# Sheet_1_2024-10-24.net
KiCad netlist of a schematic drawn in Altium Designer
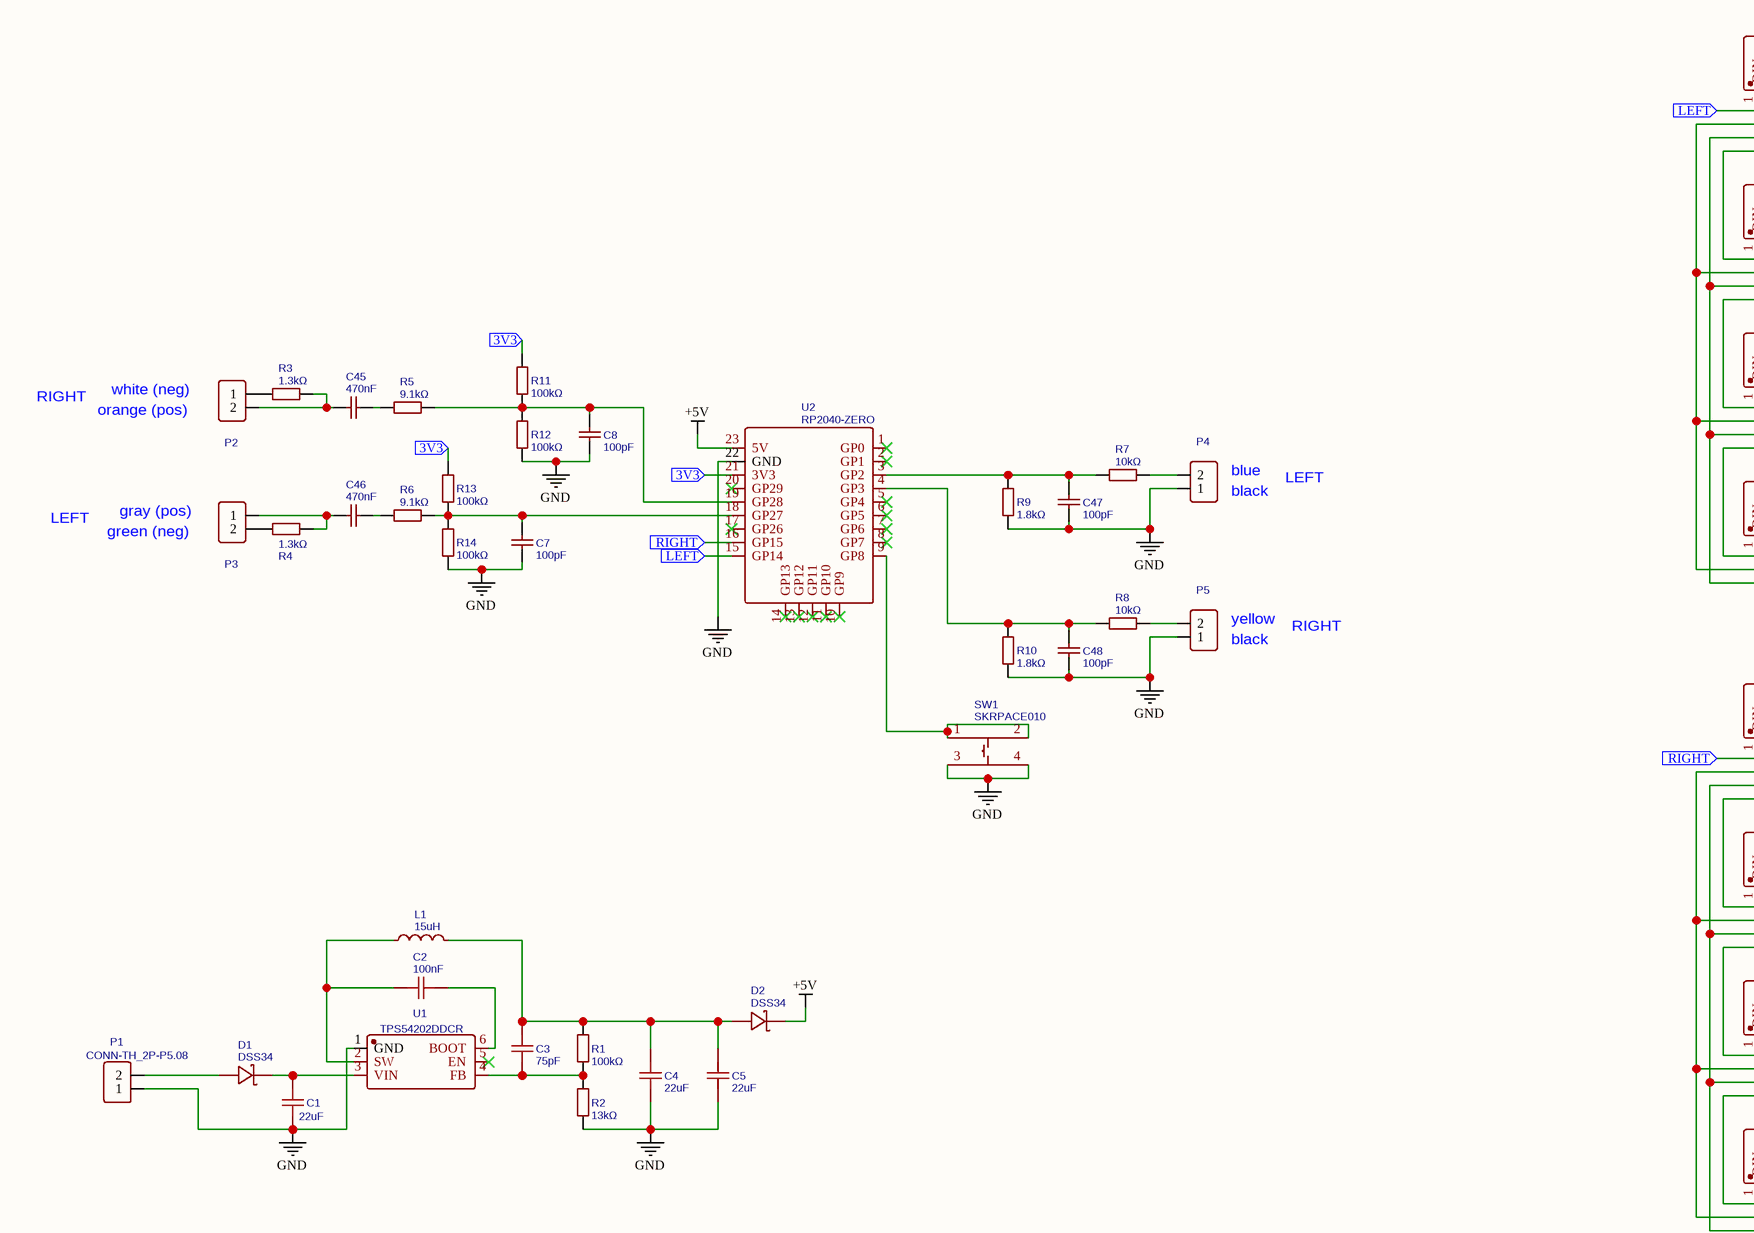
[diagram p0: Sheet_1_2024-10-24.schdoc, left]
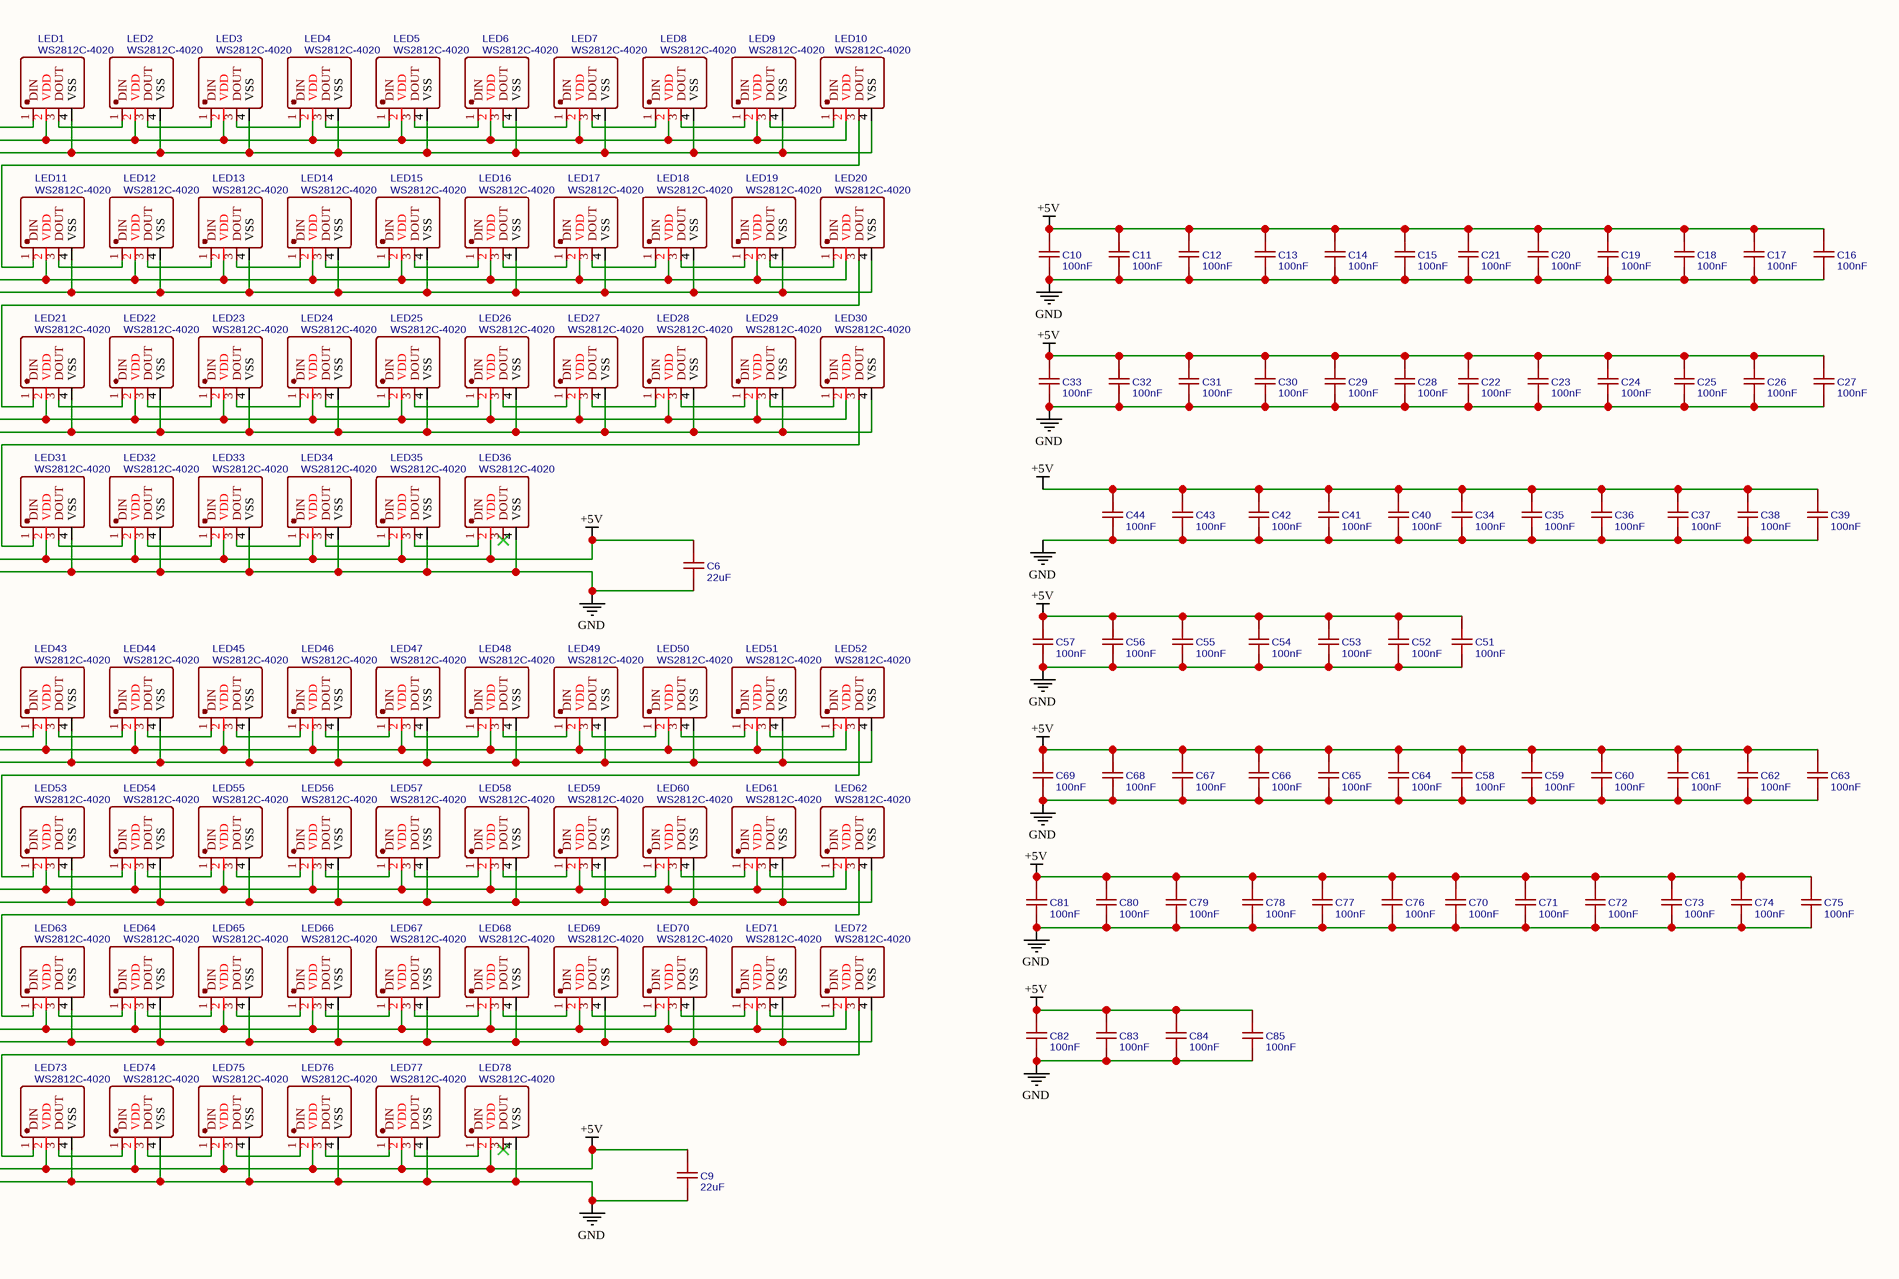
[diagram p1: Sheet_1_2024-10-24.schdoc, right]

(export (version "E")
  (design (tool "Eeschema 10.0.6"))
  (components
    (comp (ref "C1")
      (value "22uF")
      (fields
        (field (name "MANUFACTURER") "Samsung Electro-Mechanics")
        (field (name "MANUFACTURER PART") "CL21A226MAYNNNE")
        (field (name "CONTRIBUTOR") "LCSC")
      )
      (libsource (lib "altium-import") (part "root_1_22uF_"))
    )
    (comp (ref "C2")
      (value "100nF")
      (fields
        (field (name "MANUFACTURER PART") "CL05B104KO5NNNC")
        (field (name "MANUFACTURER") "SAMSUNG(三星)")
      )
      (libsource (lib "altium-import") (part "root_2_100nF_"))
    )
    (comp (ref "C3")
      (value "75pF")
      (fields
        (field (name "MANUFACTURER") "YAGEO(国巨)")
        (field (name "MANUFACTURER PART") "CC0603JRNPO9BN750")
        (field (name "CONTRIBUTOR") "LCSC")
      )
      (libsource (lib "altium-import") (part "root_0_75pF_"))
    )
    (comp (ref "C4")
      (value "22uF")
      (fields (field (name "MANUFACTURER") "SAMSUNG") (field (name "MANUFACTURER PART") "CL10A226MQ8NRNC"))
      (libsource (lib "altium-import") (part "root_1_22uF_"))
    )
    (comp (ref "C5")
      (value "22uF")
      (fields (field (name "MANUFACTURER") "SAMSUNG") (field (name "MANUFACTURER PART") "CL10A226MQ8NRNC"))
      (libsource (lib "altium-import") (part "root_1_22uF_"))
    )
    (comp (ref "C6")
      (value "22uF")
      (fields (field (name "MANUFACTURER") "SAMSUNG") (field (name "MANUFACTURER PART") "CL10A226MQ8NRNC"))
      (libsource (lib "altium-import") (part "root_1_22uF_"))
    )
    (comp (ref "C7")
      (value "100pF")
      (fields
        (field (name "MANUFACTURER PART") "CL10C101JB8NNNC")
        (field (name "MANUFACTURER") "SAMSUNG(三星)")
      )
      (libsource (lib "altium-import") (part "root_1_100pF_"))
    )
    (comp (ref "C8")
      (value "100pF")
      (fields
        (field (name "MANUFACTURER PART") "CL10C101JB8NNNC")
        (field (name "MANUFACTURER") "SAMSUNG(三星)")
      )
      (libsource (lib "altium-import") (part "root_1_100pF_"))
    )
    (comp (ref "C9")
      (value "22uF")
      (fields (field (name "MANUFACTURER") "SAMSUNG") (field (name "MANUFACTURER PART") "CL10A226MQ8NRNC"))
      (libsource (lib "altium-import") (part "root_1_22uF_"))
    )
    (comp (ref "C10")
      (value "100nF")
      (fields
        (field (name "MANUFACTURER PART") "CL05B104KO5NNNC")
        (field (name "MANUFACTURER") "SAMSUNG(三星)")
      )
      (libsource (lib "altium-import") (part "root_1_100nF_"))
    )
    (comp (ref "C11")
      (value "100nF")
      (fields
        (field (name "MANUFACTURER PART") "CL05B104KO5NNNC")
        (field (name "MANUFACTURER") "SAMSUNG(三星)")
      )
      (libsource (lib "altium-import") (part "root_1_100nF_"))
    )
    (comp (ref "C12")
      (value "100nF")
      (fields
        (field (name "MANUFACTURER PART") "CL05B104KO5NNNC")
        (field (name "MANUFACTURER") "SAMSUNG(三星)")
      )
      (libsource (lib "altium-import") (part "root_1_100nF_"))
    )
    (comp (ref "C13")
      (value "100nF")
      (fields
        (field (name "MANUFACTURER PART") "CL05B104KO5NNNC")
        (field (name "MANUFACTURER") "SAMSUNG(三星)")
      )
      (libsource (lib "altium-import") (part "root_1_100nF_"))
    )
    (comp (ref "C14")
      (value "100nF")
      (fields
        (field (name "MANUFACTURER PART") "CL05B104KO5NNNC")
        (field (name "MANUFACTURER") "SAMSUNG(三星)")
      )
      (libsource (lib "altium-import") (part "root_1_100nF_"))
    )
    (comp (ref "C15")
      (value "100nF")
      (fields
        (field (name "MANUFACTURER PART") "CL05B104KO5NNNC")
        (field (name "MANUFACTURER") "SAMSUNG(三星)")
      )
      (libsource (lib "altium-import") (part "root_1_100nF_"))
    )
    (comp (ref "C16")
      (value "100nF")
      (fields
        (field (name "MANUFACTURER PART") "CL05B104KO5NNNC")
        (field (name "MANUFACTURER") "SAMSUNG(三星)")
      )
      (libsource (lib "altium-import") (part "root_1_100nF_"))
    )
    (comp (ref "C17")
      (value "100nF")
      (fields
        (field (name "MANUFACTURER PART") "CL05B104KO5NNNC")
        (field (name "MANUFACTURER") "SAMSUNG(三星)")
      )
      (libsource (lib "altium-import") (part "root_1_100nF_"))
    )
    (comp (ref "C18")
      (value "100nF")
      (fields
        (field (name "MANUFACTURER PART") "CL05B104KO5NNNC")
        (field (name "MANUFACTURER") "SAMSUNG(三星)")
      )
      (libsource (lib "altium-import") (part "root_1_100nF_"))
    )
    (comp (ref "C19")
      (value "100nF")
      (fields
        (field (name "MANUFACTURER PART") "CL05B104KO5NNNC")
        (field (name "MANUFACTURER") "SAMSUNG(三星)")
      )
      (libsource (lib "altium-import") (part "root_1_100nF_"))
    )
    (comp (ref "C20")
      (value "100nF")
      (fields
        (field (name "MANUFACTURER PART") "CL05B104KO5NNNC")
        (field (name "MANUFACTURER") "SAMSUNG(三星)")
      )
      (libsource (lib "altium-import") (part "root_1_100nF_"))
    )
    (comp (ref "C21")
      (value "100nF")
      (fields
        (field (name "MANUFACTURER PART") "CL05B104KO5NNNC")
        (field (name "MANUFACTURER") "SAMSUNG(三星)")
      )
      (libsource (lib "altium-import") (part "root_1_100nF_"))
    )
    (comp (ref "C22")
      (value "100nF")
      (fields
        (field (name "MANUFACTURER PART") "CL05B104KO5NNNC")
        (field (name "MANUFACTURER") "SAMSUNG(三星)")
      )
      (libsource (lib "altium-import") (part "root_1_100nF_"))
    )
    (comp (ref "C23")
      (value "100nF")
      (fields
        (field (name "MANUFACTURER PART") "CL05B104KO5NNNC")
        (field (name "MANUFACTURER") "SAMSUNG(三星)")
      )
      (libsource (lib "altium-import") (part "root_1_100nF_"))
    )
    (comp (ref "C24")
      (value "100nF")
      (fields
        (field (name "MANUFACTURER PART") "CL05B104KO5NNNC")
        (field (name "MANUFACTURER") "SAMSUNG(三星)")
      )
      (libsource (lib "altium-import") (part "root_1_100nF_"))
    )
    (comp (ref "C25")
      (value "100nF")
      (fields
        (field (name "MANUFACTURER PART") "CL05B104KO5NNNC")
        (field (name "MANUFACTURER") "SAMSUNG(三星)")
      )
      (libsource (lib "altium-import") (part "root_1_100nF_"))
    )
    (comp (ref "C26")
      (value "100nF")
      (fields
        (field (name "MANUFACTURER PART") "CL05B104KO5NNNC")
        (field (name "MANUFACTURER") "SAMSUNG(三星)")
      )
      (libsource (lib "altium-import") (part "root_1_100nF_"))
    )
    (comp (ref "C27")
      (value "100nF")
      (fields
        (field (name "MANUFACTURER PART") "CL05B104KO5NNNC")
        (field (name "MANUFACTURER") "SAMSUNG(三星)")
      )
      (libsource (lib "altium-import") (part "root_1_100nF_"))
    )
    (comp (ref "C28")
      (value "100nF")
      (fields
        (field (name "MANUFACTURER PART") "CL05B104KO5NNNC")
        (field (name "MANUFACTURER") "SAMSUNG(三星)")
      )
      (libsource (lib "altium-import") (part "root_1_100nF_"))
    )
    (comp (ref "C29")
      (value "100nF")
      (fields
        (field (name "MANUFACTURER PART") "CL05B104KO5NNNC")
        (field (name "MANUFACTURER") "SAMSUNG(三星)")
      )
      (libsource (lib "altium-import") (part "root_1_100nF_"))
    )
    (comp (ref "C30")
      (value "100nF")
      (fields
        (field (name "MANUFACTURER PART") "CL05B104KO5NNNC")
        (field (name "MANUFACTURER") "SAMSUNG(三星)")
      )
      (libsource (lib "altium-import") (part "root_1_100nF_"))
    )
    (comp (ref "C31")
      (value "100nF")
      (fields
        (field (name "MANUFACTURER PART") "CL05B104KO5NNNC")
        (field (name "MANUFACTURER") "SAMSUNG(三星)")
      )
      (libsource (lib "altium-import") (part "root_1_100nF_"))
    )
    (comp (ref "C32")
      (value "100nF")
      (fields
        (field (name "MANUFACTURER PART") "CL05B104KO5NNNC")
        (field (name "MANUFACTURER") "SAMSUNG(三星)")
      )
      (libsource (lib "altium-import") (part "root_1_100nF_"))
    )
    (comp (ref "C33")
      (value "100nF")
      (fields
        (field (name "MANUFACTURER PART") "CL05B104KO5NNNC")
        (field (name "MANUFACTURER") "SAMSUNG(三星)")
      )
      (libsource (lib "altium-import") (part "root_1_100nF_"))
    )
    (comp (ref "C34")
      (value "100nF")
      (fields
        (field (name "MANUFACTURER PART") "CL05B104KO5NNNC")
        (field (name "MANUFACTURER") "SAMSUNG(三星)")
      )
      (libsource (lib "altium-import") (part "root_1_100nF_"))
    )
    (comp (ref "C35")
      (value "100nF")
      (fields
        (field (name "MANUFACTURER PART") "CL05B104KO5NNNC")
        (field (name "MANUFACTURER") "SAMSUNG(三星)")
      )
      (libsource (lib "altium-import") (part "root_1_100nF_"))
    )
    (comp (ref "C36")
      (value "100nF")
      (fields
        (field (name "MANUFACTURER PART") "CL05B104KO5NNNC")
        (field (name "MANUFACTURER") "SAMSUNG(三星)")
      )
      (libsource (lib "altium-import") (part "root_1_100nF_"))
    )
    (comp (ref "C37")
      (value "100nF")
      (fields
        (field (name "MANUFACTURER PART") "CL05B104KO5NNNC")
        (field (name "MANUFACTURER") "SAMSUNG(三星)")
      )
      (libsource (lib "altium-import") (part "root_1_100nF_"))
    )
    (comp (ref "C38")
      (value "100nF")
      (fields
        (field (name "MANUFACTURER PART") "CL05B104KO5NNNC")
        (field (name "MANUFACTURER") "SAMSUNG(三星)")
      )
      (libsource (lib "altium-import") (part "root_1_100nF_"))
    )
    (comp (ref "C39")
      (value "100nF")
      (fields
        (field (name "MANUFACTURER PART") "CL05B104KO5NNNC")
        (field (name "MANUFACTURER") "SAMSUNG(三星)")
      )
      (libsource (lib "altium-import") (part "root_1_100nF_"))
    )
    (comp (ref "C40")
      (value "100nF")
      (fields
        (field (name "MANUFACTURER PART") "CL05B104KO5NNNC")
        (field (name "MANUFACTURER") "SAMSUNG(三星)")
      )
      (libsource (lib "altium-import") (part "root_1_100nF_"))
    )
    (comp (ref "C41")
      (value "100nF")
      (fields
        (field (name "MANUFACTURER PART") "CL05B104KO5NNNC")
        (field (name "MANUFACTURER") "SAMSUNG(三星)")
      )
      (libsource (lib "altium-import") (part "root_1_100nF_"))
    )
    (comp (ref "C42")
      (value "100nF")
      (fields
        (field (name "MANUFACTURER PART") "CL05B104KO5NNNC")
        (field (name "MANUFACTURER") "SAMSUNG(三星)")
      )
      (libsource (lib "altium-import") (part "root_1_100nF_"))
    )
    (comp (ref "C43")
      (value "100nF")
      (fields
        (field (name "MANUFACTURER PART") "CL05B104KO5NNNC")
        (field (name "MANUFACTURER") "SAMSUNG(三星)")
      )
      (libsource (lib "altium-import") (part "root_1_100nF_"))
    )
    (comp (ref "C44")
      (value "100nF")
      (fields
        (field (name "MANUFACTURER PART") "CL05B104KO5NNNC")
        (field (name "MANUFACTURER") "SAMSUNG(三星)")
      )
      (libsource (lib "altium-import") (part "root_1_100nF_"))
    )
    (comp (ref "C45")
      (value "470nF")
      (fields
        (field (name "MANUFACTURER PART") "CL21B474KBFNNNE")
        (field (name "MANUFACTURER") "SAMSUNG(三星)")
      )
      (libsource (lib "altium-import") (part "root_0_470nF_"))
    )
    (comp (ref "C46")
      (value "470nF")
      (fields
        (field (name "MANUFACTURER PART") "CL21B474KBFNNNE")
        (field (name "MANUFACTURER") "SAMSUNG(三星)")
      )
      (libsource (lib "altium-import") (part "root_0_470nF_"))
    )
    (comp (ref "C47")
      (value "100pF")
      (fields
        (field (name "MANUFACTURER PART") "CL10C101JB8NNNC")
        (field (name "MANUFACTURER") "SAMSUNG(三星)")
      )
      (libsource (lib "altium-import") (part "root_1_100pF_"))
    )
    (comp (ref "C48")
      (value "100pF")
      (fields
        (field (name "MANUFACTURER PART") "CL10C101JB8NNNC")
        (field (name "MANUFACTURER") "SAMSUNG(三星)")
      )
      (libsource (lib "altium-import") (part "root_1_100pF_"))
    )
    (comp (ref "C51")
      (value "100nF")
      (fields
        (field (name "MANUFACTURER PART") "CL05B104KO5NNNC")
        (field (name "MANUFACTURER") "SAMSUNG(三星)")
      )
      (libsource (lib "altium-import") (part "root_1_100nF_"))
    )
    (comp (ref "C52")
      (value "100nF")
      (fields
        (field (name "MANUFACTURER PART") "CL05B104KO5NNNC")
        (field (name "MANUFACTURER") "SAMSUNG(三星)")
      )
      (libsource (lib "altium-import") (part "root_1_100nF_"))
    )
    (comp (ref "C53")
      (value "100nF")
      (fields
        (field (name "MANUFACTURER PART") "CL05B104KO5NNNC")
        (field (name "MANUFACTURER") "SAMSUNG(三星)")
      )
      (libsource (lib "altium-import") (part "root_1_100nF_"))
    )
    (comp (ref "C54")
      (value "100nF")
      (fields
        (field (name "MANUFACTURER PART") "CL05B104KO5NNNC")
        (field (name "MANUFACTURER") "SAMSUNG(三星)")
      )
      (libsource (lib "altium-import") (part "root_1_100nF_"))
    )
    (comp (ref "C55")
      (value "100nF")
      (fields
        (field (name "MANUFACTURER PART") "CL05B104KO5NNNC")
        (field (name "MANUFACTURER") "SAMSUNG(三星)")
      )
      (libsource (lib "altium-import") (part "root_1_100nF_"))
    )
    (comp (ref "C56")
      (value "100nF")
      (fields
        (field (name "MANUFACTURER PART") "CL05B104KO5NNNC")
        (field (name "MANUFACTURER") "SAMSUNG(三星)")
      )
      (libsource (lib "altium-import") (part "root_1_100nF_"))
    )
    (comp (ref "C57")
      (value "100nF")
      (fields
        (field (name "MANUFACTURER PART") "CL05B104KO5NNNC")
        (field (name "MANUFACTURER") "SAMSUNG(三星)")
      )
      (libsource (lib "altium-import") (part "root_1_100nF_"))
    )
    (comp (ref "C58")
      (value "100nF")
      (fields
        (field (name "MANUFACTURER PART") "CL05B104KO5NNNC")
        (field (name "MANUFACTURER") "SAMSUNG(三星)")
      )
      (libsource (lib "altium-import") (part "root_1_100nF_"))
    )
    (comp (ref "C59")
      (value "100nF")
      (fields
        (field (name "MANUFACTURER PART") "CL05B104KO5NNNC")
        (field (name "MANUFACTURER") "SAMSUNG(三星)")
      )
      (libsource (lib "altium-import") (part "root_1_100nF_"))
    )
    (comp (ref "C60")
      (value "100nF")
      (fields
        (field (name "MANUFACTURER PART") "CL05B104KO5NNNC")
        (field (name "MANUFACTURER") "SAMSUNG(三星)")
      )
      (libsource (lib "altium-import") (part "root_1_100nF_"))
    )
    (comp (ref "C61")
      (value "100nF")
      (fields
        (field (name "MANUFACTURER PART") "CL05B104KO5NNNC")
        (field (name "MANUFACTURER") "SAMSUNG(三星)")
      )
      (libsource (lib "altium-import") (part "root_1_100nF_"))
    )
    (comp (ref "C62")
      (value "100nF")
      (fields
        (field (name "MANUFACTURER PART") "CL05B104KO5NNNC")
        (field (name "MANUFACTURER") "SAMSUNG(三星)")
      )
      (libsource (lib "altium-import") (part "root_1_100nF_"))
    )
    (comp (ref "C63")
      (value "100nF")
      (fields
        (field (name "MANUFACTURER PART") "CL05B104KO5NNNC")
        (field (name "MANUFACTURER") "SAMSUNG(三星)")
      )
      (libsource (lib "altium-import") (part "root_1_100nF_"))
    )
    (comp (ref "C64")
      (value "100nF")
      (fields
        (field (name "MANUFACTURER PART") "CL05B104KO5NNNC")
        (field (name "MANUFACTURER") "SAMSUNG(三星)")
      )
      (libsource (lib "altium-import") (part "root_1_100nF_"))
    )
    (comp (ref "C65")
      (value "100nF")
      (fields
        (field (name "MANUFACTURER PART") "CL05B104KO5NNNC")
        (field (name "MANUFACTURER") "SAMSUNG(三星)")
      )
      (libsource (lib "altium-import") (part "root_1_100nF_"))
    )
    (comp (ref "C66")
      (value "100nF")
      (fields
        (field (name "MANUFACTURER PART") "CL05B104KO5NNNC")
        (field (name "MANUFACTURER") "SAMSUNG(三星)")
      )
      (libsource (lib "altium-import") (part "root_1_100nF_"))
    )
    (comp (ref "C67")
      (value "100nF")
      (fields
        (field (name "MANUFACTURER PART") "CL05B104KO5NNNC")
        (field (name "MANUFACTURER") "SAMSUNG(三星)")
      )
      (libsource (lib "altium-import") (part "root_1_100nF_"))
    )
    (comp (ref "C68")
      (value "100nF")
      (fields
        (field (name "MANUFACTURER PART") "CL05B104KO5NNNC")
        (field (name "MANUFACTURER") "SAMSUNG(三星)")
      )
      (libsource (lib "altium-import") (part "root_1_100nF_"))
    )
    (comp (ref "C69")
      (value "100nF")
      (fields
        (field (name "MANUFACTURER PART") "CL05B104KO5NNNC")
        (field (name "MANUFACTURER") "SAMSUNG(三星)")
      )
      (libsource (lib "altium-import") (part "root_1_100nF_"))
    )
    (comp (ref "C70")
      (value "100nF")
      (fields
        (field (name "MANUFACTURER PART") "CL05B104KO5NNNC")
        (field (name "MANUFACTURER") "SAMSUNG(三星)")
      )
      (libsource (lib "altium-import") (part "root_1_100nF_"))
    )
    (comp (ref "C71")
      (value "100nF")
      (fields
        (field (name "MANUFACTURER PART") "CL05B104KO5NNNC")
        (field (name "MANUFACTURER") "SAMSUNG(三星)")
      )
      (libsource (lib "altium-import") (part "root_1_100nF_"))
    )
    (comp (ref "C72")
      (value "100nF")
      (fields
        (field (name "MANUFACTURER PART") "CL05B104KO5NNNC")
        (field (name "MANUFACTURER") "SAMSUNG(三星)")
      )
      (libsource (lib "altium-import") (part "root_1_100nF_"))
    )
    (comp (ref "C73")
      (value "100nF")
      (fields
        (field (name "MANUFACTURER PART") "CL05B104KO5NNNC")
        (field (name "MANUFACTURER") "SAMSUNG(三星)")
      )
      (libsource (lib "altium-import") (part "root_1_100nF_"))
    )
    (comp (ref "C74")
      (value "100nF")
      (fields
        (field (name "MANUFACTURER PART") "CL05B104KO5NNNC")
        (field (name "MANUFACTURER") "SAMSUNG(三星)")
      )
      (libsource (lib "altium-import") (part "root_1_100nF_"))
    )
    (comp (ref "C75")
      (value "100nF")
      (fields
        (field (name "MANUFACTURER PART") "CL05B104KO5NNNC")
        (field (name "MANUFACTURER") "SAMSUNG(三星)")
      )
      (libsource (lib "altium-import") (part "root_1_100nF_"))
    )
    (comp (ref "C76")
      (value "100nF")
      (fields
        (field (name "MANUFACTURER PART") "CL05B104KO5NNNC")
        (field (name "MANUFACTURER") "SAMSUNG(三星)")
      )
      (libsource (lib "altium-import") (part "root_1_100nF_"))
    )
    (comp (ref "C77")
      (value "100nF")
      (fields
        (field (name "MANUFACTURER PART") "CL05B104KO5NNNC")
        (field (name "MANUFACTURER") "SAMSUNG(三星)")
      )
      (libsource (lib "altium-import") (part "root_1_100nF_"))
    )
    (comp (ref "C78")
      (value "100nF")
      (fields
        (field (name "MANUFACTURER PART") "CL05B104KO5NNNC")
        (field (name "MANUFACTURER") "SAMSUNG(三星)")
      )
      (libsource (lib "altium-import") (part "root_1_100nF_"))
    )
    (comp (ref "C79")
      (value "100nF")
      (fields
        (field (name "MANUFACTURER PART") "CL05B104KO5NNNC")
        (field (name "MANUFACTURER") "SAMSUNG(三星)")
      )
      (libsource (lib "altium-import") (part "root_1_100nF_"))
    )
    (comp (ref "C80")
      (value "100nF")
      (fields
        (field (name "MANUFACTURER PART") "CL05B104KO5NNNC")
        (field (name "MANUFACTURER") "SAMSUNG(三星)")
      )
      (libsource (lib "altium-import") (part "root_1_100nF_"))
    )
    (comp (ref "C81")
      (value "100nF")
      (fields
        (field (name "MANUFACTURER PART") "CL05B104KO5NNNC")
        (field (name "MANUFACTURER") "SAMSUNG(三星)")
      )
      (libsource (lib "altium-import") (part "root_1_100nF_"))
    )
    (comp (ref "C82")
      (value "100nF")
      (fields
        (field (name "MANUFACTURER PART") "CL05B104KO5NNNC")
        (field (name "MANUFACTURER") "SAMSUNG(三星)")
      )
      (libsource (lib "altium-import") (part "root_1_100nF_"))
    )
    (comp (ref "C83")
      (value "100nF")
      (fields
        (field (name "MANUFACTURER PART") "CL05B104KO5NNNC")
        (field (name "MANUFACTURER") "SAMSUNG(三星)")
      )
      (libsource (lib "altium-import") (part "root_1_100nF_"))
    )
    (comp (ref "C84")
      (value "100nF")
      (fields
        (field (name "MANUFACTURER PART") "CL05B104KO5NNNC")
        (field (name "MANUFACTURER") "SAMSUNG(三星)")
      )
      (libsource (lib "altium-import") (part "root_1_100nF_"))
    )
    (comp (ref "C85")
      (value "100nF")
      (fields
        (field (name "MANUFACTURER PART") "CL05B104KO5NNNC")
        (field (name "MANUFACTURER") "SAMSUNG(三星)")
      )
      (libsource (lib "altium-import") (part "root_1_100nF_"))
    )
    (comp (ref "D1")
      (value "DSS34")
      (fields (field (name "MANUFACTURER") "STARSEA"))
      (libsource (lib "altium-import") (part "root_2_DSS34_"))
    )
    (comp (ref "D2")
      (value "DSS34")
      (fields (field (name "MANUFACTURER") "STARSEA"))
      (libsource (lib "altium-import") (part "root_2_DSS34_"))
    )
    (comp (ref "L1")
      (value "15uH")
      (fields
        (field (name "MANUFACTURER") "Sunltech(韩国顺磁)")
        (field (name "MANUFACTURER PART") "SLP6028S150MTT")
        (field (name "CONTRIBUTOR") "LCSC")
      )
      (libsource (lib "altium-import") (part "root_0_15uH_"))
    )
    (comp (ref "LED1")
      (value "WS2812C-4020")
      (fields (field (name "MANUFACTURER") "worldsemi") (field (name "CONTRIBUTOR") "lcsc"))
      (libsource (lib "altium-import") (part "root_1_WS2812C-4020_"))
    )
    (comp (ref "LED2")
      (value "WS2812C-4020")
      (fields (field (name "MANUFACTURER") "worldsemi") (field (name "CONTRIBUTOR") "lcsc"))
      (libsource (lib "altium-import") (part "root_1_WS2812C-4020_"))
    )
    (comp (ref "LED3")
      (value "WS2812C-4020")
      (fields (field (name "MANUFACTURER") "worldsemi") (field (name "CONTRIBUTOR") "lcsc"))
      (libsource (lib "altium-import") (part "root_1_WS2812C-4020_"))
    )
    (comp (ref "LED4")
      (value "WS2812C-4020")
      (fields (field (name "MANUFACTURER") "worldsemi") (field (name "CONTRIBUTOR") "lcsc"))
      (libsource (lib "altium-import") (part "root_1_WS2812C-4020_"))
    )
    (comp (ref "LED5")
      (value "WS2812C-4020")
      (fields (field (name "MANUFACTURER") "worldsemi") (field (name "CONTRIBUTOR") "lcsc"))
      (libsource (lib "altium-import") (part "root_1_WS2812C-4020_"))
    )
    (comp (ref "LED6")
      (value "WS2812C-4020")
      (fields (field (name "MANUFACTURER") "worldsemi") (field (name "CONTRIBUTOR") "lcsc"))
      (libsource (lib "altium-import") (part "root_1_WS2812C-4020_"))
    )
    (comp (ref "LED7")
      (value "WS2812C-4020")
      (fields (field (name "MANUFACTURER") "worldsemi") (field (name "CONTRIBUTOR") "lcsc"))
      (libsource (lib "altium-import") (part "root_1_WS2812C-4020_"))
    )
    (comp (ref "LED8")
      (value "WS2812C-4020")
      (fields (field (name "MANUFACTURER") "worldsemi") (field (name "CONTRIBUTOR") "lcsc"))
      (libsource (lib "altium-import") (part "root_1_WS2812C-4020_"))
    )
    (comp (ref "LED9")
      (value "WS2812C-4020")
      (fields (field (name "MANUFACTURER") "worldsemi") (field (name "CONTRIBUTOR") "lcsc"))
      (libsource (lib "altium-import") (part "root_1_WS2812C-4020_"))
    )
    (comp (ref "LED10")
      (value "WS2812C-4020")
      (fields (field (name "MANUFACTURER") "worldsemi") (field (name "CONTRIBUTOR") "lcsc"))
      (libsource (lib "altium-import") (part "root_1_WS2812C-4020_"))
    )
    (comp (ref "LED11")
      (value "WS2812C-4020")
      (fields (field (name "MANUFACTURER") "worldsemi") (field (name "CONTRIBUTOR") "lcsc"))
      (libsource (lib "altium-import") (part "root_1_WS2812C-4020_"))
    )
    (comp (ref "LED12")
      (value "WS2812C-4020")
      (fields (field (name "MANUFACTURER") "worldsemi") (field (name "CONTRIBUTOR") "lcsc"))
      (libsource (lib "altium-import") (part "root_1_WS2812C-4020_"))
    )
    (comp (ref "LED13")
      (value "WS2812C-4020")
      (fields (field (name "MANUFACTURER") "worldsemi") (field (name "CONTRIBUTOR") "lcsc"))
      (libsource (lib "altium-import") (part "root_1_WS2812C-4020_"))
    )
    (comp (ref "LED14")
      (value "WS2812C-4020")
      (fields (field (name "MANUFACTURER") "worldsemi") (field (name "CONTRIBUTOR") "lcsc"))
      (libsource (lib "altium-import") (part "root_1_WS2812C-4020_"))
    )
    (comp (ref "LED15")
      (value "WS2812C-4020")
      (fields (field (name "MANUFACTURER") "worldsemi") (field (name "CONTRIBUTOR") "lcsc"))
      (libsource (lib "altium-import") (part "root_1_WS2812C-4020_"))
    )
    (comp (ref "LED16")
      (value "WS2812C-4020")
      (fields (field (name "MANUFACTURER") "worldsemi") (field (name "CONTRIBUTOR") "lcsc"))
      (libsource (lib "altium-import") (part "root_1_WS2812C-4020_"))
    )
    (comp (ref "LED17")
      (value "WS2812C-4020")
      (fields (field (name "MANUFACTURER") "worldsemi") (field (name "CONTRIBUTOR") "lcsc"))
      (libsource (lib "altium-import") (part "root_1_WS2812C-4020_"))
    )
    (comp (ref "LED18")
      (value "WS2812C-4020")
      (fields (field (name "MANUFACTURER") "worldsemi") (field (name "CONTRIBUTOR") "lcsc"))
      (libsource (lib "altium-import") (part "root_1_WS2812C-4020_"))
    )
    (comp (ref "LED19")
      (value "WS2812C-4020")
      (fields (field (name "MANUFACTURER") "worldsemi") (field (name "CONTRIBUTOR") "lcsc"))
      (libsource (lib "altium-import") (part "root_1_WS2812C-4020_"))
    )
    (comp (ref "LED20")
      (value "WS2812C-4020")
      (fields (field (name "MANUFACTURER") "worldsemi") (field (name "CONTRIBUTOR") "lcsc"))
      (libsource (lib "altium-import") (part "root_1_WS2812C-4020_"))
    )
    (comp (ref "LED21")
      (value "WS2812C-4020")
      (fields (field (name "MANUFACTURER") "worldsemi") (field (name "CONTRIBUTOR") "lcsc"))
      (libsource (lib "altium-import") (part "root_1_WS2812C-4020_"))
    )
    (comp (ref "LED22")
      (value "WS2812C-4020")
      (fields (field (name "MANUFACTURER") "worldsemi") (field (name "CONTRIBUTOR") "lcsc"))
      (libsource (lib "altium-import") (part "root_1_WS2812C-4020_"))
    )
    (comp (ref "LED23")
      (value "WS2812C-4020")
      (fields (field (name "MANUFACTURER") "worldsemi") (field (name "CONTRIBUTOR") "lcsc"))
      (libsource (lib "altium-import") (part "root_1_WS2812C-4020_"))
    )
    (comp (ref "LED24")
      (value "WS2812C-4020")
      (fields (field (name "MANUFACTURER") "worldsemi") (field (name "CONTRIBUTOR") "lcsc"))
      (libsource (lib "altium-import") (part "root_1_WS2812C-4020_"))
    )
    (comp (ref "LED25")
      (value "WS2812C-4020")
      (fields (field (name "MANUFACTURER") "worldsemi") (field (name "CONTRIBUTOR") "lcsc"))
      (libsource (lib "altium-import") (part "root_1_WS2812C-4020_"))
    )
    (comp (ref "LED26")
      (value "WS2812C-4020")
      (fields (field (name "MANUFACTURER") "worldsemi") (field (name "CONTRIBUTOR") "lcsc"))
      (libsource (lib "altium-import") (part "root_1_WS2812C-4020_"))
    )
    (comp (ref "LED27")
      (value "WS2812C-4020")
      (fields (field (name "MANUFACTURER") "worldsemi") (field (name "CONTRIBUTOR") "lcsc"))
      (libsource (lib "altium-import") (part "root_1_WS2812C-4020_"))
    )
    (comp (ref "LED28")
      (value "WS2812C-4020")
      (fields (field (name "MANUFACTURER") "worldsemi") (field (name "CONTRIBUTOR") "lcsc"))
      (libsource (lib "altium-import") (part "root_1_WS2812C-4020_"))
    )
    (comp (ref "LED29")
      (value "WS2812C-4020")
      (fields (field (name "MANUFACTURER") "worldsemi") (field (name "CONTRIBUTOR") "lcsc"))
      (libsource (lib "altium-import") (part "root_1_WS2812C-4020_"))
    )
    (comp (ref "LED30")
      (value "WS2812C-4020")
      (fields (field (name "MANUFACTURER") "worldsemi") (field (name "CONTRIBUTOR") "lcsc"))
      (libsource (lib "altium-import") (part "root_1_WS2812C-4020_"))
    )
    (comp (ref "LED31")
      (value "WS2812C-4020")
      (fields (field (name "MANUFACTURER") "worldsemi") (field (name "CONTRIBUTOR") "lcsc"))
      (libsource (lib "altium-import") (part "root_1_WS2812C-4020_"))
    )
    (comp (ref "LED32")
      (value "WS2812C-4020")
      (fields (field (name "MANUFACTURER") "worldsemi") (field (name "CONTRIBUTOR") "lcsc"))
      (libsource (lib "altium-import") (part "root_1_WS2812C-4020_"))
    )
    (comp (ref "LED33")
      (value "WS2812C-4020")
      (fields (field (name "MANUFACTURER") "worldsemi") (field (name "CONTRIBUTOR") "lcsc"))
      (libsource (lib "altium-import") (part "root_1_WS2812C-4020_"))
    )
    (comp (ref "LED34")
      (value "WS2812C-4020")
      (fields (field (name "MANUFACTURER") "worldsemi") (field (name "CONTRIBUTOR") "lcsc"))
      (libsource (lib "altium-import") (part "root_1_WS2812C-4020_"))
    )
    (comp (ref "LED35")
      (value "WS2812C-4020")
      (fields (field (name "MANUFACTURER") "worldsemi") (field (name "CONTRIBUTOR") "lcsc"))
      (libsource (lib "altium-import") (part "root_1_WS2812C-4020_"))
    )
    (comp (ref "LED36")
      (value "WS2812C-4020")
      (fields (field (name "MANUFACTURER") "worldsemi") (field (name "CONTRIBUTOR") "lcsc"))
      (libsource (lib "altium-import") (part "root_1_WS2812C-4020_"))
    )
    (comp (ref "LED43")
      (value "WS2812C-4020")
      (fields (field (name "MANUFACTURER") "worldsemi") (field (name "CONTRIBUTOR") "lcsc"))
      (libsource (lib "altium-import") (part "root_1_WS2812C-4020_"))
    )
    (comp (ref "LED44")
      (value "WS2812C-4020")
      (fields (field (name "MANUFACTURER") "worldsemi") (field (name "CONTRIBUTOR") "lcsc"))
      (libsource (lib "altium-import") (part "root_1_WS2812C-4020_"))
    )
    (comp (ref "LED45")
      (value "WS2812C-4020")
      (fields (field (name "MANUFACTURER") "worldsemi") (field (name "CONTRIBUTOR") "lcsc"))
      (libsource (lib "altium-import") (part "root_1_WS2812C-4020_"))
    )
    (comp (ref "LED46")
      (value "WS2812C-4020")
      (fields (field (name "MANUFACTURER") "worldsemi") (field (name "CONTRIBUTOR") "lcsc"))
      (libsource (lib "altium-import") (part "root_1_WS2812C-4020_"))
    )
    (comp (ref "LED47")
      (value "WS2812C-4020")
      (fields (field (name "MANUFACTURER") "worldsemi") (field (name "CONTRIBUTOR") "lcsc"))
      (libsource (lib "altium-import") (part "root_1_WS2812C-4020_"))
    )
    (comp (ref "LED48")
      (value "WS2812C-4020")
      (fields (field (name "MANUFACTURER") "worldsemi") (field (name "CONTRIBUTOR") "lcsc"))
      (libsource (lib "altium-import") (part "root_1_WS2812C-4020_"))
    )
    (comp (ref "LED49")
      (value "WS2812C-4020")
      (fields (field (name "MANUFACTURER") "worldsemi") (field (name "CONTRIBUTOR") "lcsc"))
      (libsource (lib "altium-import") (part "root_1_WS2812C-4020_"))
    )
    (comp (ref "LED50")
      (value "WS2812C-4020")
      (fields (field (name "MANUFACTURER") "worldsemi") (field (name "CONTRIBUTOR") "lcsc"))
      (libsource (lib "altium-import") (part "root_1_WS2812C-4020_"))
    )
    (comp (ref "LED51")
      (value "WS2812C-4020")
      (fields (field (name "MANUFACTURER") "worldsemi") (field (name "CONTRIBUTOR") "lcsc"))
      (libsource (lib "altium-import") (part "root_1_WS2812C-4020_"))
    )
    (comp (ref "LED52")
      (value "WS2812C-4020")
      (fields (field (name "MANUFACTURER") "worldsemi") (field (name "CONTRIBUTOR") "lcsc"))
      (libsource (lib "altium-import") (part "root_1_WS2812C-4020_"))
    )
    (comp (ref "LED53")
      (value "WS2812C-4020")
      (fields (field (name "MANUFACTURER") "worldsemi") (field (name "CONTRIBUTOR") "lcsc"))
      (libsource (lib "altium-import") (part "root_1_WS2812C-4020_"))
    )
    (comp (ref "LED54")
      (value "WS2812C-4020")
      (fields (field (name "MANUFACTURER") "worldsemi") (field (name "CONTRIBUTOR") "lcsc"))
      (libsource (lib "altium-import") (part "root_1_WS2812C-4020_"))
    )
    (comp (ref "LED55")
      (value "WS2812C-4020")
      (fields (field (name "MANUFACTURER") "worldsemi") (field (name "CONTRIBUTOR") "lcsc"))
      (libsource (lib "altium-import") (part "root_1_WS2812C-4020_"))
    )
    (comp (ref "LED56")
      (value "WS2812C-4020")
      (fields (field (name "MANUFACTURER") "worldsemi") (field (name "CONTRIBUTOR") "lcsc"))
      (libsource (lib "altium-import") (part "root_1_WS2812C-4020_"))
    )
    (comp (ref "LED57")
      (value "WS2812C-4020")
      (fields (field (name "MANUFACTURER") "worldsemi") (field (name "CONTRIBUTOR") "lcsc"))
      (libsource (lib "altium-import") (part "root_1_WS2812C-4020_"))
    )
    (comp (ref "LED58")
      (value "WS2812C-4020")
      (fields (field (name "MANUFACTURER") "worldsemi") (field (name "CONTRIBUTOR") "lcsc"))
      (libsource (lib "altium-import") (part "root_1_WS2812C-4020_"))
    )
    (comp (ref "LED59")
      (value "WS2812C-4020")
      (fields (field (name "MANUFACTURER") "worldsemi") (field (name "CONTRIBUTOR") "lcsc"))
      (libsource (lib "altium-import") (part "root_1_WS2812C-4020_"))
    )
    (comp (ref "LED60")
      (value "WS2812C-4020")
      (fields (field (name "MANUFACTURER") "worldsemi") (field (name "CONTRIBUTOR") "lcsc"))
      (libsource (lib "altium-import") (part "root_1_WS2812C-4020_"))
    )
    (comp (ref "LED61")
      (value "WS2812C-4020")
      (fields (field (name "MANUFACTURER") "worldsemi") (field (name "CONTRIBUTOR") "lcsc"))
      (libsource (lib "altium-import") (part "root_1_WS2812C-4020_"))
    )
    (comp (ref "LED62")
      (value "WS2812C-4020")
      (fields (field (name "MANUFACTURER") "worldsemi") (field (name "CONTRIBUTOR") "lcsc"))
      (libsource (lib "altium-import") (part "root_1_WS2812C-4020_"))
    )
    (comp (ref "LED63")
      (value "WS2812C-4020")
      (fields (field (name "MANUFACTURER") "worldsemi") (field (name "CONTRIBUTOR") "lcsc"))
      (libsource (lib "altium-import") (part "root_1_WS2812C-4020_"))
    )
    (comp (ref "LED64")
      (value "WS2812C-4020")
      (fields (field (name "MANUFACTURER") "worldsemi") (field (name "CONTRIBUTOR") "lcsc"))
      (libsource (lib "altium-import") (part "root_1_WS2812C-4020_"))
    )
    (comp (ref "LED65")
      (value "WS2812C-4020")
      (fields (field (name "MANUFACTURER") "worldsemi") (field (name "CONTRIBUTOR") "lcsc"))
      (libsource (lib "altium-import") (part "root_1_WS2812C-4020_"))
    )
    (comp (ref "LED66")
      (value "WS2812C-4020")
      (fields (field (name "MANUFACTURER") "worldsemi") (field (name "CONTRIBUTOR") "lcsc"))
      (libsource (lib "altium-import") (part "root_1_WS2812C-4020_"))
    )
    (comp (ref "LED67")
      (value "WS2812C-4020")
      (fields (field (name "MANUFACTURER") "worldsemi") (field (name "CONTRIBUTOR") "lcsc"))
      (libsource (lib "altium-import") (part "root_1_WS2812C-4020_"))
    )
    (comp (ref "LED68")
      (value "WS2812C-4020")
      (fields (field (name "MANUFACTURER") "worldsemi") (field (name "CONTRIBUTOR") "lcsc"))
      (libsource (lib "altium-import") (part "root_1_WS2812C-4020_"))
    )
    (comp (ref "LED69")
      (value "WS2812C-4020")
      (fields (field (name "MANUFACTURER") "worldsemi") (field (name "CONTRIBUTOR") "lcsc"))
      (libsource (lib "altium-import") (part "root_1_WS2812C-4020_"))
    )
    (comp (ref "LED70")
      (value "WS2812C-4020")
      (fields (field (name "MANUFACTURER") "worldsemi") (field (name "CONTRIBUTOR") "lcsc"))
      (libsource (lib "altium-import") (part "root_1_WS2812C-4020_"))
    )
    (comp (ref "LED71")
      (value "WS2812C-4020")
      (fields (field (name "MANUFACTURER") "worldsemi") (field (name "CONTRIBUTOR") "lcsc"))
      (libsource (lib "altium-import") (part "root_1_WS2812C-4020_"))
    )
    (comp (ref "LED72")
      (value "WS2812C-4020")
      (fields (field (name "MANUFACTURER") "worldsemi") (field (name "CONTRIBUTOR") "lcsc"))
      (libsource (lib "altium-import") (part "root_1_WS2812C-4020_"))
    )
    (comp (ref "LED73")
      (value "WS2812C-4020")
      (fields (field (name "MANUFACTURER") "worldsemi") (field (name "CONTRIBUTOR") "lcsc"))
      (libsource (lib "altium-import") (part "root_1_WS2812C-4020_"))
    )
    (comp (ref "LED74")
      (value "WS2812C-4020")
      (fields (field (name "MANUFACTURER") "worldsemi") (field (name "CONTRIBUTOR") "lcsc"))
      (libsource (lib "altium-import") (part "root_1_WS2812C-4020_"))
    )
    (comp (ref "LED75")
      (value "WS2812C-4020")
      (fields (field (name "MANUFACTURER") "worldsemi") (field (name "CONTRIBUTOR") "lcsc"))
      (libsource (lib "altium-import") (part "root_1_WS2812C-4020_"))
    )
    (comp (ref "LED76")
      (value "WS2812C-4020")
      (fields (field (name "MANUFACTURER") "worldsemi") (field (name "CONTRIBUTOR") "lcsc"))
      (libsource (lib "altium-import") (part "root_1_WS2812C-4020_"))
    )
    (comp (ref "LED77")
      (value "WS2812C-4020")
      (fields (field (name "MANUFACTURER") "worldsemi") (field (name "CONTRIBUTOR") "lcsc"))
      (libsource (lib "altium-import") (part "root_1_WS2812C-4020_"))
    )
    (comp (ref "LED78")
      (value "WS2812C-4020")
      (fields (field (name "MANUFACTURER") "worldsemi") (field (name "CONTRIBUTOR") "lcsc"))
      (libsource (lib "altium-import") (part "root_1_WS2812C-4020_"))
    )
    (comp (ref "P1")
      (value "CONN-TH_2P-P5.08")
      (fields (field (name "CONTRIBUTOR") "LCEDA_Lib"))
      (libsource (lib "") (part "root_2_CONN-TH_2P-P5.08__2"))
    )
    (comp (ref "P2")
      (value "CONN-TH_2P-P5.08")
      (fields (field (name "CONTRIBUTOR") "LCEDA_Lib"))
      (libsource (lib "") (part "root_2_CONN-TH_2P-P5.08__1"))
    )
    (comp (ref "P3")
      (value "CONN-TH_2P-P5.08")
      (fields (field (name "CONTRIBUTOR") "LCEDA_Lib"))
      (libsource (lib "") (part "root_2_CONN-TH_2P-P5.08__1"))
    )
    (comp (ref "P4")
      (value "CONN-TH_2P-P5.08")
      (fields (field (name "CONTRIBUTOR") "LCEDA_Lib"))
      (libsource (lib "altium-import") (part "root_2_CONN-TH_2P-P5.08_"))
    )
    (comp (ref "P5")
      (value "CONN-TH_2P-P5.08")
      (fields (field (name "CONTRIBUTOR") "LCEDA_Lib"))
      (libsource (lib "altium-import") (part "root_2_CONN-TH_2P-P5.08_"))
    )
    (comp (ref "R1")
      (value "100kΩ")
      (fields
        (field (name "MANUFACTURER") "UNI-ROYAL(厚声)")
        (field (name "MANUFACTURER PART") "0603WAF1003T5E")
      )
      (libsource (lib "altium-import") (part "root_1_100kΩ_"))
    )
    (comp (ref "R2")
      (value "13kΩ")
      (fields
        (field (name "MANUFACTURER") "UNI-ROYAL(厚声)")
        (field (name "MANUFACTURER PART") "0603WAF1302T5E")
      )
      (libsource (lib "altium-import") (part "root_1_13kΩ_"))
    )
    (comp (ref "R3")
      (value "1.3kΩ")
      (fields
        (field (name "MANUFACTURER") "UNI-ROYAL(厚声)")
        (field (name "MANUFACTURER PART") "0603WAF1301T5E")
      )
      (libsource (lib "altium-import") (part "root_0_1.3kΩ_"))
    )
    (comp (ref "R4")
      (value "1.3kΩ")
      (fields
        (field (name "MANUFACTURER") "UNI-ROYAL(厚声)")
        (field (name "MANUFACTURER PART") "0603WAF1301T5E")
      )
      (libsource (lib "altium-import") (part "root_0_1.3kΩ_"))
    )
    (comp (ref "R5")
      (value "9.1kΩ")
      (fields
        (field (name "MANUFACTURER") "UNI-ROYAL(厚声)")
        (field (name "MANUFACTURER PART") "0603WAF9101T5E")
      )
      (libsource (lib "altium-import") (part "root_0_9.1kΩ_"))
    )
    (comp (ref "R6")
      (value "9.1kΩ")
      (fields
        (field (name "MANUFACTURER") "UNI-ROYAL(厚声)")
        (field (name "MANUFACTURER PART") "0603WAF9101T5E")
      )
      (libsource (lib "altium-import") (part "root_0_9.1kΩ_"))
    )
    (comp (ref "R7")
      (value "10kΩ")
      (fields
        (field (name "MANUFACTURER") "UNI-ROYAL(厚声)")
        (field (name "MANUFACTURER PART") "0603WAF1002T5E")
      )
      (libsource (lib "altium-import") (part "root_0_10kΩ_"))
    )
    (comp (ref "R8")
      (value "10kΩ")
      (fields
        (field (name "MANUFACTURER") "UNI-ROYAL(厚声)")
        (field (name "MANUFACTURER PART") "0603WAF1002T5E")
      )
      (libsource (lib "altium-import") (part "root_0_10kΩ_"))
    )
    (comp (ref "R9")
      (value "1.8kΩ")
      (fields
        (field (name "MANUFACTURER") "UNI-ROYAL(厚声)")
        (field (name "MANUFACTURER PART") "0603WAF1801T5E")
      )
      (libsource (lib "altium-import") (part "root_1_1.8kΩ_"))
    )
    (comp (ref "R10")
      (value "1.8kΩ")
      (fields
        (field (name "MANUFACTURER") "UNI-ROYAL(厚声)")
        (field (name "MANUFACTURER PART") "0603WAF1801T5E")
      )
      (libsource (lib "altium-import") (part "root_1_1.8kΩ_"))
    )
    (comp (ref "R11")
      (value "100kΩ")
      (fields
        (field (name "MANUFACTURER") "UNI-ROYAL(厚声)")
        (field (name "MANUFACTURER PART") "0603WAF1003T5E")
      )
      (libsource (lib "altium-import") (part "root_1_100kΩ_"))
    )
    (comp (ref "R12")
      (value "100kΩ")
      (fields
        (field (name "MANUFACTURER") "UNI-ROYAL(厚声)")
        (field (name "MANUFACTURER PART") "0603WAF1003T5E")
      )
      (libsource (lib "altium-import") (part "root_1_100kΩ_"))
    )
    (comp (ref "R13")
      (value "100kΩ")
      (fields
        (field (name "MANUFACTURER") "UNI-ROYAL(厚声)")
        (field (name "MANUFACTURER PART") "0603WAF1003T5E")
      )
      (libsource (lib "altium-import") (part "root_1_100kΩ_"))
    )
    (comp (ref "R14")
      (value "100kΩ")
      (fields
        (field (name "MANUFACTURER") "UNI-ROYAL(厚声)")
        (field (name "MANUFACTURER PART") "0603WAF1003T5E")
      )
      (libsource (lib "altium-import") (part "root_1_100kΩ_"))
    )
    (comp (ref "SW1")
      (value "SKRPACE010")
      (fields (field (name "MANUFACTURER") "ALPSALPINE(阿尔卑斯阿尔派)") (field (name "CONTRIBUTOR") "LCSC"))
      (libsource (lib "altium-import") (part "root_0_SKRPACE010_"))
    )
    (comp (ref "U1")
      (value "TPS54202DDCR")
      (fields (field (name "MANUFACTURER") "TI(德州仪器)") (field (name "CONTRIBUTOR") "LCSC"))
      (libsource (lib "altium-import") (part "root_0_TPS54202DDCR_"))
    )
    (comp (ref "U2")
      (value "RP2040-ZERO")
      (fields
        (field (name "MANUFACTURER") "Waveshare(微雪电子)")
        (field (name "MANUFACTURER PART") "RP2040-Zero")
        (field (name "CONTRIBUTOR") "lcsc")
      )
      (libsource (lib "altium-import") (part "root_0_RP2040-ZERO_"))
    )
  )
  (nets
    (net (code "1") (name "+5V") (class "Default")
      (node (ref "C10") (pin "2") (pinfunction "2_2") (pintype "passive"))
      (node (ref "C11") (pin "2") (pinfunction "2_2") (pintype "passive"))
      (node (ref "C12") (pin "2") (pinfunction "2_2") (pintype "passive"))
      (node (ref "C13") (pin "2") (pinfunction "2_2") (pintype "passive"))
      (node (ref "C14") (pin "2") (pinfunction "2_2") (pintype "passive"))
      (node (ref "C15") (pin "2") (pinfunction "2_2") (pintype "passive"))
      (node (ref "C16") (pin "2") (pinfunction "2_2") (pintype "passive"))
      (node (ref "C17") (pin "2") (pinfunction "2_2") (pintype "passive"))
      (node (ref "C18") (pin "2") (pinfunction "2_2") (pintype "passive"))
      (node (ref "C19") (pin "2") (pinfunction "2_2") (pintype "passive"))
      (node (ref "C20") (pin "2") (pinfunction "2_2") (pintype "passive"))
      (node (ref "C21") (pin "2") (pinfunction "2_2") (pintype "passive"))
      (node (ref "C22") (pin "2") (pinfunction "2_2") (pintype "passive"))
      (node (ref "C23") (pin "2") (pinfunction "2_2") (pintype "passive"))
      (node (ref "C24") (pin "2") (pinfunction "2_2") (pintype "passive"))
      (node (ref "C25") (pin "2") (pinfunction "2_2") (pintype "passive"))
      (node (ref "C26") (pin "2") (pinfunction "2_2") (pintype "passive"))
      (node (ref "C27") (pin "2") (pinfunction "2_2") (pintype "passive"))
      (node (ref "C28") (pin "2") (pinfunction "2_2") (pintype "passive"))
      (node (ref "C29") (pin "2") (pinfunction "2_2") (pintype "passive"))
      (node (ref "C30") (pin "2") (pinfunction "2_2") (pintype "passive"))
      (node (ref "C31") (pin "2") (pinfunction "2_2") (pintype "passive"))
      (node (ref "C32") (pin "2") (pinfunction "2_2") (pintype "passive"))
      (node (ref "C33") (pin "2") (pinfunction "2_2") (pintype "passive"))
      (node (ref "C34") (pin "2") (pinfunction "2_2") (pintype "passive"))
      (node (ref "C35") (pin "2") (pinfunction "2_2") (pintype "passive"))
      (node (ref "C36") (pin "2") (pinfunction "2_2") (pintype "passive"))
      (node (ref "C37") (pin "2") (pinfunction "2_2") (pintype "passive"))
      (node (ref "C38") (pin "2") (pinfunction "2_2") (pintype "passive"))
      (node (ref "C39") (pin "2") (pinfunction "2_2") (pintype "passive"))
      (node (ref "C40") (pin "2") (pinfunction "2_2") (pintype "passive"))
      (node (ref "C41") (pin "2") (pinfunction "2_2") (pintype "passive"))
      (node (ref "C42") (pin "2") (pinfunction "2_2") (pintype "passive"))
      (node (ref "C43") (pin "2") (pinfunction "2_2") (pintype "passive"))
      (node (ref "C44") (pin "2") (pinfunction "2_2") (pintype "passive"))
      (node (ref "C51") (pin "2") (pinfunction "2_2") (pintype "passive"))
      (node (ref "C52") (pin "2") (pinfunction "2_2") (pintype "passive"))
      (node (ref "C53") (pin "2") (pinfunction "2_2") (pintype "passive"))
      (node (ref "C54") (pin "2") (pinfunction "2_2") (pintype "passive"))
      (node (ref "C55") (pin "2") (pinfunction "2_2") (pintype "passive"))
      (node (ref "C56") (pin "2") (pinfunction "2_2") (pintype "passive"))
      (node (ref "C57") (pin "2") (pinfunction "2_2") (pintype "passive"))
      (node (ref "C58") (pin "2") (pinfunction "2_2") (pintype "passive"))
      (node (ref "C59") (pin "2") (pinfunction "2_2") (pintype "passive"))
      (node (ref "C6") (pin "2") (pinfunction "2_2") (pintype "passive"))
      (node (ref "C60") (pin "2") (pinfunction "2_2") (pintype "passive"))
      (node (ref "C61") (pin "2") (pinfunction "2_2") (pintype "passive"))
      (node (ref "C62") (pin "2") (pinfunction "2_2") (pintype "passive"))
      (node (ref "C63") (pin "2") (pinfunction "2_2") (pintype "passive"))
      (node (ref "C64") (pin "2") (pinfunction "2_2") (pintype "passive"))
      (node (ref "C65") (pin "2") (pinfunction "2_2") (pintype "passive"))
      (node (ref "C66") (pin "2") (pinfunction "2_2") (pintype "passive"))
      (node (ref "C67") (pin "2") (pinfunction "2_2") (pintype "passive"))
      (node (ref "C68") (pin "2") (pinfunction "2_2") (pintype "passive"))
      (node (ref "C69") (pin "2") (pinfunction "2_2") (pintype "passive"))
      (node (ref "C70") (pin "2") (pinfunction "2_2") (pintype "passive"))
      (node (ref "C71") (pin "2") (pinfunction "2_2") (pintype "passive"))
      (node (ref "C72") (pin "2") (pinfunction "2_2") (pintype "passive"))
      (node (ref "C73") (pin "2") (pinfunction "2_2") (pintype "passive"))
      (node (ref "C74") (pin "2") (pinfunction "2_2") (pintype "passive"))
      (node (ref "C75") (pin "2") (pinfunction "2_2") (pintype "passive"))
      (node (ref "C76") (pin "2") (pinfunction "2_2") (pintype "passive"))
      (node (ref "C77") (pin "2") (pinfunction "2_2") (pintype "passive"))
      (node (ref "C78") (pin "2") (pinfunction "2_2") (pintype "passive"))
      (node (ref "C79") (pin "2") (pinfunction "2_2") (pintype "passive"))
      (node (ref "C80") (pin "2") (pinfunction "2_2") (pintype "passive"))
      (node (ref "C81") (pin "2") (pinfunction "2_2") (pintype "passive"))
      (node (ref "C82") (pin "2") (pinfunction "2_2") (pintype "passive"))
      (node (ref "C83") (pin "2") (pinfunction "2_2") (pintype "passive"))
      (node (ref "C84") (pin "2") (pinfunction "2_2") (pintype "passive"))
      (node (ref "C85") (pin "2") (pinfunction "2_2") (pintype "passive"))
      (node (ref "C9") (pin "2") (pinfunction "2_2") (pintype "passive"))
      (node (ref "D2") (pin "1") (pinfunction "K_1") (pintype "passive"))
      (node (ref "LED1") (pin "2") (pinfunction "VDD_2") (pintype "passive"))
      (node (ref "LED10") (pin "2") (pinfunction "VDD_2") (pintype "passive"))
      (node (ref "LED11") (pin "2") (pinfunction "VDD_2") (pintype "passive"))
      (node (ref "LED12") (pin "2") (pinfunction "VDD_2") (pintype "passive"))
      (node (ref "LED13") (pin "2") (pinfunction "VDD_2") (pintype "passive"))
      (node (ref "LED14") (pin "2") (pinfunction "VDD_2") (pintype "passive"))
      (node (ref "LED15") (pin "2") (pinfunction "VDD_2") (pintype "passive"))
      (node (ref "LED16") (pin "2") (pinfunction "VDD_2") (pintype "passive"))
      (node (ref "LED17") (pin "2") (pinfunction "VDD_2") (pintype "passive"))
      (node (ref "LED18") (pin "2") (pinfunction "VDD_2") (pintype "passive"))
      (node (ref "LED19") (pin "2") (pinfunction "VDD_2") (pintype "passive"))
      (node (ref "LED2") (pin "2") (pinfunction "VDD_2") (pintype "passive"))
      (node (ref "LED20") (pin "2") (pinfunction "VDD_2") (pintype "passive"))
      (node (ref "LED21") (pin "2") (pinfunction "VDD_2") (pintype "passive"))
      (node (ref "LED22") (pin "2") (pinfunction "VDD_2") (pintype "passive"))
      (node (ref "LED23") (pin "2") (pinfunction "VDD_2") (pintype "passive"))
      (node (ref "LED24") (pin "2") (pinfunction "VDD_2") (pintype "passive"))
      (node (ref "LED25") (pin "2") (pinfunction "VDD_2") (pintype "passive"))
      (node (ref "LED26") (pin "2") (pinfunction "VDD_2") (pintype "passive"))
      (node (ref "LED27") (pin "2") (pinfunction "VDD_2") (pintype "passive"))
      (node (ref "LED28") (pin "2") (pinfunction "VDD_2") (pintype "passive"))
      (node (ref "LED29") (pin "2") (pinfunction "VDD_2") (pintype "passive"))
      (node (ref "LED3") (pin "2") (pinfunction "VDD_2") (pintype "passive"))
      (node (ref "LED30") (pin "2") (pinfunction "VDD_2") (pintype "passive"))
      (node (ref "LED31") (pin "2") (pinfunction "VDD_2") (pintype "passive"))
      (node (ref "LED32") (pin "2") (pinfunction "VDD_2") (pintype "passive"))
      (node (ref "LED33") (pin "2") (pinfunction "VDD_2") (pintype "passive"))
      (node (ref "LED34") (pin "2") (pinfunction "VDD_2") (pintype "passive"))
      (node (ref "LED35") (pin "2") (pinfunction "VDD_2") (pintype "passive"))
      (node (ref "LED36") (pin "2") (pinfunction "VDD_2") (pintype "passive"))
      (node (ref "LED4") (pin "2") (pinfunction "VDD_2") (pintype "passive"))
      (node (ref "LED43") (pin "2") (pinfunction "VDD_2") (pintype "passive"))
      (node (ref "LED44") (pin "2") (pinfunction "VDD_2") (pintype "passive"))
      (node (ref "LED45") (pin "2") (pinfunction "VDD_2") (pintype "passive"))
      (node (ref "LED46") (pin "2") (pinfunction "VDD_2") (pintype "passive"))
      (node (ref "LED47") (pin "2") (pinfunction "VDD_2") (pintype "passive"))
      (node (ref "LED48") (pin "2") (pinfunction "VDD_2") (pintype "passive"))
      (node (ref "LED49") (pin "2") (pinfunction "VDD_2") (pintype "passive"))
      (node (ref "LED5") (pin "2") (pinfunction "VDD_2") (pintype "passive"))
      (node (ref "LED50") (pin "2") (pinfunction "VDD_2") (pintype "passive"))
      (node (ref "LED51") (pin "2") (pinfunction "VDD_2") (pintype "passive"))
      (node (ref "LED52") (pin "2") (pinfunction "VDD_2") (pintype "passive"))
      (node (ref "LED53") (pin "2") (pinfunction "VDD_2") (pintype "passive"))
      (node (ref "LED54") (pin "2") (pinfunction "VDD_2") (pintype "passive"))
      (node (ref "LED55") (pin "2") (pinfunction "VDD_2") (pintype "passive"))
      (node (ref "LED56") (pin "2") (pinfunction "VDD_2") (pintype "passive"))
      (node (ref "LED57") (pin "2") (pinfunction "VDD_2") (pintype "passive"))
      (node (ref "LED58") (pin "2") (pinfunction "VDD_2") (pintype "passive"))
      (node (ref "LED59") (pin "2") (pinfunction "VDD_2") (pintype "passive"))
      (node (ref "LED6") (pin "2") (pinfunction "VDD_2") (pintype "passive"))
      (node (ref "LED60") (pin "2") (pinfunction "VDD_2") (pintype "passive"))
      (node (ref "LED61") (pin "2") (pinfunction "VDD_2") (pintype "passive"))
      (node (ref "LED62") (pin "2") (pinfunction "VDD_2") (pintype "passive"))
      (node (ref "LED63") (pin "2") (pinfunction "VDD_2") (pintype "passive"))
      (node (ref "LED64") (pin "2") (pinfunction "VDD_2") (pintype "passive"))
      (node (ref "LED65") (pin "2") (pinfunction "VDD_2") (pintype "passive"))
      (node (ref "LED66") (pin "2") (pinfunction "VDD_2") (pintype "passive"))
      (node (ref "LED67") (pin "2") (pinfunction "VDD_2") (pintype "passive"))
      (node (ref "LED68") (pin "2") (pinfunction "VDD_2") (pintype "passive"))
      (node (ref "LED69") (pin "2") (pinfunction "VDD_2") (pintype "passive"))
      (node (ref "LED7") (pin "2") (pinfunction "VDD_2") (pintype "passive"))
      (node (ref "LED70") (pin "2") (pinfunction "VDD_2") (pintype "passive"))
      (node (ref "LED71") (pin "2") (pinfunction "VDD_2") (pintype "passive"))
      (node (ref "LED72") (pin "2") (pinfunction "VDD_2") (pintype "passive"))
      (node (ref "LED73") (pin "2") (pinfunction "VDD_2") (pintype "passive"))
      (node (ref "LED74") (pin "2") (pinfunction "VDD_2") (pintype "passive"))
      (node (ref "LED75") (pin "2") (pinfunction "VDD_2") (pintype "passive"))
      (node (ref "LED76") (pin "2") (pinfunction "VDD_2") (pintype "passive"))
      (node (ref "LED77") (pin "2") (pinfunction "VDD_2") (pintype "passive"))
      (node (ref "LED78") (pin "2") (pinfunction "VDD_2") (pintype "passive"))
      (node (ref "LED8") (pin "2") (pinfunction "VDD_2") (pintype "passive"))
      (node (ref "LED9") (pin "2") (pinfunction "VDD_2") (pintype "passive"))
      (node (ref "U2") (pin "23") (pinfunction "5V_23") (pintype "passive"))
    )
    (net (code "2") (name "/3V3") (class "Default")
      (node (ref "R11") (pin "2") (pinfunction "2_2") (pintype "passive"))
      (node (ref "R13") (pin "2") (pinfunction "2_2") (pintype "passive"))
      (node (ref "U2") (pin "21") (pinfunction "3V3_21") (pintype "passive"))
    )
    (net (code "3") (name "/LEFT") (class "Default")
      (node (ref "LED1") (pin "1") (pinfunction "DIN_1") (pintype "passive"))
      (node (ref "U2") (pin "15") (pinfunction "GP14_15") (pintype "passive"))
    )
    (net (code "4") (name "/RIGHT") (class "Default")
      (node (ref "LED43") (pin "1") (pinfunction "DIN_1") (pintype "passive"))
      (node (ref "U2") (pin "16") (pinfunction "GP15_16") (pintype "passive"))
    )
    (net (code "5") (name "GND") (class "Default")
      (node (ref "C1") (pin "1") (pinfunction "1_1") (pintype "passive"))
      (node (ref "C10") (pin "1") (pinfunction "1_1") (pintype "passive"))
      (node (ref "C11") (pin "1") (pinfunction "1_1") (pintype "passive"))
      (node (ref "C12") (pin "1") (pinfunction "1_1") (pintype "passive"))
      (node (ref "C13") (pin "1") (pinfunction "1_1") (pintype "passive"))
      (node (ref "C14") (pin "1") (pinfunction "1_1") (pintype "passive"))
      (node (ref "C15") (pin "1") (pinfunction "1_1") (pintype "passive"))
      (node (ref "C16") (pin "1") (pinfunction "1_1") (pintype "passive"))
      (node (ref "C17") (pin "1") (pinfunction "1_1") (pintype "passive"))
      (node (ref "C18") (pin "1") (pinfunction "1_1") (pintype "passive"))
      (node (ref "C19") (pin "1") (pinfunction "1_1") (pintype "passive"))
      (node (ref "C20") (pin "1") (pinfunction "1_1") (pintype "passive"))
      (node (ref "C21") (pin "1") (pinfunction "1_1") (pintype "passive"))
      (node (ref "C22") (pin "1") (pinfunction "1_1") (pintype "passive"))
      (node (ref "C23") (pin "1") (pinfunction "1_1") (pintype "passive"))
      (node (ref "C24") (pin "1") (pinfunction "1_1") (pintype "passive"))
      (node (ref "C25") (pin "1") (pinfunction "1_1") (pintype "passive"))
      (node (ref "C26") (pin "1") (pinfunction "1_1") (pintype "passive"))
      (node (ref "C27") (pin "1") (pinfunction "1_1") (pintype "passive"))
      (node (ref "C28") (pin "1") (pinfunction "1_1") (pintype "passive"))
      (node (ref "C29") (pin "1") (pinfunction "1_1") (pintype "passive"))
      (node (ref "C30") (pin "1") (pinfunction "1_1") (pintype "passive"))
      (node (ref "C31") (pin "1") (pinfunction "1_1") (pintype "passive"))
      (node (ref "C32") (pin "1") (pinfunction "1_1") (pintype "passive"))
      (node (ref "C33") (pin "1") (pinfunction "1_1") (pintype "passive"))
      (node (ref "C34") (pin "1") (pinfunction "1_1") (pintype "passive"))
      (node (ref "C35") (pin "1") (pinfunction "1_1") (pintype "passive"))
      (node (ref "C36") (pin "1") (pinfunction "1_1") (pintype "passive"))
      (node (ref "C37") (pin "1") (pinfunction "1_1") (pintype "passive"))
      (node (ref "C38") (pin "1") (pinfunction "1_1") (pintype "passive"))
      (node (ref "C39") (pin "1") (pinfunction "1_1") (pintype "passive"))
      (node (ref "C4") (pin "1") (pinfunction "1_1") (pintype "passive"))
      (node (ref "C40") (pin "1") (pinfunction "1_1") (pintype "passive"))
      (node (ref "C41") (pin "1") (pinfunction "1_1") (pintype "passive"))
      (node (ref "C42") (pin "1") (pinfunction "1_1") (pintype "passive"))
      (node (ref "C43") (pin "1") (pinfunction "1_1") (pintype "passive"))
      (node (ref "C44") (pin "1") (pinfunction "1_1") (pintype "passive"))
      (node (ref "C47") (pin "1") (pinfunction "1_1") (pintype "passive"))
      (node (ref "C48") (pin "1") (pinfunction "1_1") (pintype "passive"))
      (node (ref "C5") (pin "1") (pinfunction "1_1") (pintype "passive"))
      (node (ref "C51") (pin "1") (pinfunction "1_1") (pintype "passive"))
      (node (ref "C52") (pin "1") (pinfunction "1_1") (pintype "passive"))
      (node (ref "C53") (pin "1") (pinfunction "1_1") (pintype "passive"))
      (node (ref "C54") (pin "1") (pinfunction "1_1") (pintype "passive"))
      (node (ref "C55") (pin "1") (pinfunction "1_1") (pintype "passive"))
      (node (ref "C56") (pin "1") (pinfunction "1_1") (pintype "passive"))
      (node (ref "C57") (pin "1") (pinfunction "1_1") (pintype "passive"))
      (node (ref "C58") (pin "1") (pinfunction "1_1") (pintype "passive"))
      (node (ref "C59") (pin "1") (pinfunction "1_1") (pintype "passive"))
      (node (ref "C6") (pin "1") (pinfunction "1_1") (pintype "passive"))
      (node (ref "C60") (pin "1") (pinfunction "1_1") (pintype "passive"))
      (node (ref "C61") (pin "1") (pinfunction "1_1") (pintype "passive"))
      (node (ref "C62") (pin "1") (pinfunction "1_1") (pintype "passive"))
      (node (ref "C63") (pin "1") (pinfunction "1_1") (pintype "passive"))
      (node (ref "C64") (pin "1") (pinfunction "1_1") (pintype "passive"))
      (node (ref "C65") (pin "1") (pinfunction "1_1") (pintype "passive"))
      (node (ref "C66") (pin "1") (pinfunction "1_1") (pintype "passive"))
      (node (ref "C67") (pin "1") (pinfunction "1_1") (pintype "passive"))
      (node (ref "C68") (pin "1") (pinfunction "1_1") (pintype "passive"))
      (node (ref "C69") (pin "1") (pinfunction "1_1") (pintype "passive"))
      (node (ref "C7") (pin "1") (pinfunction "1_1") (pintype "passive"))
      (node (ref "C70") (pin "1") (pinfunction "1_1") (pintype "passive"))
      (node (ref "C71") (pin "1") (pinfunction "1_1") (pintype "passive"))
      (node (ref "C72") (pin "1") (pinfunction "1_1") (pintype "passive"))
      (node (ref "C73") (pin "1") (pinfunction "1_1") (pintype "passive"))
      (node (ref "C74") (pin "1") (pinfunction "1_1") (pintype "passive"))
      (node (ref "C75") (pin "1") (pinfunction "1_1") (pintype "passive"))
      (node (ref "C76") (pin "1") (pinfunction "1_1") (pintype "passive"))
      (node (ref "C77") (pin "1") (pinfunction "1_1") (pintype "passive"))
      (node (ref "C78") (pin "1") (pinfunction "1_1") (pintype "passive"))
      (node (ref "C79") (pin "1") (pinfunction "1_1") (pintype "passive"))
      (node (ref "C8") (pin "1") (pinfunction "1_1") (pintype "passive"))
      (node (ref "C80") (pin "1") (pinfunction "1_1") (pintype "passive"))
      (node (ref "C81") (pin "1") (pinfunction "1_1") (pintype "passive"))
      (node (ref "C82") (pin "1") (pinfunction "1_1") (pintype "passive"))
      (node (ref "C83") (pin "1") (pinfunction "1_1") (pintype "passive"))
      (node (ref "C84") (pin "1") (pinfunction "1_1") (pintype "passive"))
      (node (ref "C85") (pin "1") (pinfunction "1_1") (pintype "passive"))
      (node (ref "C9") (pin "1") (pinfunction "1_1") (pintype "passive"))
      (node (ref "LED1") (pin "4") (pinfunction "VSS_4") (pintype "passive"))
      (node (ref "LED10") (pin "4") (pinfunction "VSS_4") (pintype "passive"))
      (node (ref "LED11") (pin "4") (pinfunction "VSS_4") (pintype "passive"))
      (node (ref "LED12") (pin "4") (pinfunction "VSS_4") (pintype "passive"))
      (node (ref "LED13") (pin "4") (pinfunction "VSS_4") (pintype "passive"))
      (node (ref "LED14") (pin "4") (pinfunction "VSS_4") (pintype "passive"))
      (node (ref "LED15") (pin "4") (pinfunction "VSS_4") (pintype "passive"))
      (node (ref "LED16") (pin "4") (pinfunction "VSS_4") (pintype "passive"))
      (node (ref "LED17") (pin "4") (pinfunction "VSS_4") (pintype "passive"))
      (node (ref "LED18") (pin "4") (pinfunction "VSS_4") (pintype "passive"))
      (node (ref "LED19") (pin "4") (pinfunction "VSS_4") (pintype "passive"))
      (node (ref "LED2") (pin "4") (pinfunction "VSS_4") (pintype "passive"))
      (node (ref "LED20") (pin "4") (pinfunction "VSS_4") (pintype "passive"))
      (node (ref "LED21") (pin "4") (pinfunction "VSS_4") (pintype "passive"))
      (node (ref "LED22") (pin "4") (pinfunction "VSS_4") (pintype "passive"))
      (node (ref "LED23") (pin "4") (pinfunction "VSS_4") (pintype "passive"))
      (node (ref "LED24") (pin "4") (pinfunction "VSS_4") (pintype "passive"))
      (node (ref "LED25") (pin "4") (pinfunction "VSS_4") (pintype "passive"))
      (node (ref "LED26") (pin "4") (pinfunction "VSS_4") (pintype "passive"))
      (node (ref "LED27") (pin "4") (pinfunction "VSS_4") (pintype "passive"))
      (node (ref "LED28") (pin "4") (pinfunction "VSS_4") (pintype "passive"))
      (node (ref "LED29") (pin "4") (pinfunction "VSS_4") (pintype "passive"))
      (node (ref "LED3") (pin "4") (pinfunction "VSS_4") (pintype "passive"))
      (node (ref "LED30") (pin "4") (pinfunction "VSS_4") (pintype "passive"))
      (node (ref "LED31") (pin "4") (pinfunction "VSS_4") (pintype "passive"))
      (node (ref "LED32") (pin "4") (pinfunction "VSS_4") (pintype "passive"))
      (node (ref "LED33") (pin "4") (pinfunction "VSS_4") (pintype "passive"))
      (node (ref "LED34") (pin "4") (pinfunction "VSS_4") (pintype "passive"))
      (node (ref "LED35") (pin "4") (pinfunction "VSS_4") (pintype "passive"))
      (node (ref "LED36") (pin "4") (pinfunction "VSS_4") (pintype "passive"))
      (node (ref "LED4") (pin "4") (pinfunction "VSS_4") (pintype "passive"))
      (node (ref "LED43") (pin "4") (pinfunction "VSS_4") (pintype "passive"))
      (node (ref "LED44") (pin "4") (pinfunction "VSS_4") (pintype "passive"))
      (node (ref "LED45") (pin "4") (pinfunction "VSS_4") (pintype "passive"))
      (node (ref "LED46") (pin "4") (pinfunction "VSS_4") (pintype "passive"))
      (node (ref "LED47") (pin "4") (pinfunction "VSS_4") (pintype "passive"))
      (node (ref "LED48") (pin "4") (pinfunction "VSS_4") (pintype "passive"))
      (node (ref "LED49") (pin "4") (pinfunction "VSS_4") (pintype "passive"))
      (node (ref "LED5") (pin "4") (pinfunction "VSS_4") (pintype "passive"))
      (node (ref "LED50") (pin "4") (pinfunction "VSS_4") (pintype "passive"))
      (node (ref "LED51") (pin "4") (pinfunction "VSS_4") (pintype "passive"))
      (node (ref "LED52") (pin "4") (pinfunction "VSS_4") (pintype "passive"))
      (node (ref "LED53") (pin "4") (pinfunction "VSS_4") (pintype "passive"))
      (node (ref "LED54") (pin "4") (pinfunction "VSS_4") (pintype "passive"))
      (node (ref "LED55") (pin "4") (pinfunction "VSS_4") (pintype "passive"))
      (node (ref "LED56") (pin "4") (pinfunction "VSS_4") (pintype "passive"))
      (node (ref "LED57") (pin "4") (pinfunction "VSS_4") (pintype "passive"))
      (node (ref "LED58") (pin "4") (pinfunction "VSS_4") (pintype "passive"))
      (node (ref "LED59") (pin "4") (pinfunction "VSS_4") (pintype "passive"))
      (node (ref "LED6") (pin "4") (pinfunction "VSS_4") (pintype "passive"))
      (node (ref "LED60") (pin "4") (pinfunction "VSS_4") (pintype "passive"))
      (node (ref "LED61") (pin "4") (pinfunction "VSS_4") (pintype "passive"))
      (node (ref "LED62") (pin "4") (pinfunction "VSS_4") (pintype "passive"))
      (node (ref "LED63") (pin "4") (pinfunction "VSS_4") (pintype "passive"))
      (node (ref "LED64") (pin "4") (pinfunction "VSS_4") (pintype "passive"))
      (node (ref "LED65") (pin "4") (pinfunction "VSS_4") (pintype "passive"))
      (node (ref "LED66") (pin "4") (pinfunction "VSS_4") (pintype "passive"))
      (node (ref "LED67") (pin "4") (pinfunction "VSS_4") (pintype "passive"))
      (node (ref "LED68") (pin "4") (pinfunction "VSS_4") (pintype "passive"))
      (node (ref "LED69") (pin "4") (pinfunction "VSS_4") (pintype "passive"))
      (node (ref "LED7") (pin "4") (pinfunction "VSS_4") (pintype "passive"))
      (node (ref "LED70") (pin "4") (pinfunction "VSS_4") (pintype "passive"))
      (node (ref "LED71") (pin "4") (pinfunction "VSS_4") (pintype "passive"))
      (node (ref "LED72") (pin "4") (pinfunction "VSS_4") (pintype "passive"))
      (node (ref "LED73") (pin "4") (pinfunction "VSS_4") (pintype "passive"))
      (node (ref "LED74") (pin "4") (pinfunction "VSS_4") (pintype "passive"))
      (node (ref "LED75") (pin "4") (pinfunction "VSS_4") (pintype "passive"))
      (node (ref "LED76") (pin "4") (pinfunction "VSS_4") (pintype "passive"))
      (node (ref "LED77") (pin "4") (pinfunction "VSS_4") (pintype "passive"))
      (node (ref "LED78") (pin "4") (pinfunction "VSS_4") (pintype "passive"))
      (node (ref "LED8") (pin "4") (pinfunction "VSS_4") (pintype "passive"))
      (node (ref "LED9") (pin "4") (pinfunction "VSS_4") (pintype "passive"))
      (node (ref "P1") (pin "1") (pinfunction "1_1") (pintype "passive"))
      (node (ref "P4") (pin "1") (pinfunction "1_1") (pintype "passive"))
      (node (ref "P5") (pin "1") (pinfunction "1_1") (pintype "passive"))
      (node (ref "R10") (pin "1") (pinfunction "1_1") (pintype "passive"))
      (node (ref "R12") (pin "1") (pinfunction "1_1") (pintype "passive"))
      (node (ref "R14") (pin "1") (pinfunction "1_1") (pintype "passive"))
      (node (ref "R2") (pin "1") (pinfunction "1_1") (pintype "passive"))
      (node (ref "R9") (pin "1") (pinfunction "1_1") (pintype "passive"))
      (node (ref "SW1") (pin "3") (pinfunction "3_3") (pintype "passive"))
      (node (ref "SW1") (pin "4") (pinfunction "4_4") (pintype "passive"))
      (node (ref "U1") (pin "1") (pinfunction "GND_1") (pintype "passive"))
      (node (ref "U2") (pin "22") (pinfunction "GND_22") (pintype "passive"))
    )
    (net (code "6") (name "Net-(C45-Pad1)") (class "Default")
      (node (ref "C45") (pin "1") (pinfunction "1_1") (pintype "passive"))
      (node (ref "P2") (pin "2") (pinfunction "2_2") (pintype "passive"))
      (node (ref "R3") (pin "2") (pinfunction "2_2") (pintype "passive"))
    )
    (net (code "7") (name "Net-(C45-Pad2)") (class "Default")
      (node (ref "C45") (pin "2") (pinfunction "2_2") (pintype "passive"))
      (node (ref "R5") (pin "1") (pinfunction "1_1") (pintype "passive"))
    )
    (net (code "8") (name "Net-(C46-Pad1)") (class "Default")
      (node (ref "C46") (pin "1") (pinfunction "1_1") (pintype "passive"))
      (node (ref "P3") (pin "1") (pinfunction "1_1") (pintype "passive"))
      (node (ref "R4") (pin "2") (pinfunction "2_2") (pintype "passive"))
    )
    (net (code "9") (name "Net-(C46-Pad2)") (class "Default")
      (node (ref "C46") (pin "2") (pinfunction "2_2") (pintype "passive"))
      (node (ref "R6") (pin "1") (pinfunction "1_1") (pintype "passive"))
    )
    (net (code "10") (name "Net-(D1-A)") (class "Default")
      (node (ref "D1") (pin "2") (pinfunction "A_2") (pintype "passive"))
      (node (ref "P1") (pin "2") (pinfunction "2_2") (pintype "passive"))
    )
    (net (code "11") (name "Net-(D1-K)") (class "Default")
      (node (ref "C1") (pin "2") (pinfunction "2_2") (pintype "passive"))
      (node (ref "D1") (pin "1") (pinfunction "K_1") (pintype "passive"))
      (node (ref "U1") (pin "3") (pinfunction "VIN_3") (pintype "passive"))
    )
    (net (code "12") (name "Net-(D2-A)") (class "Default")
      (node (ref "C3") (pin "2") (pinfunction "2_2") (pintype "passive"))
      (node (ref "C4") (pin "2") (pinfunction "2_2") (pintype "passive"))
      (node (ref "C5") (pin "2") (pinfunction "2_2") (pintype "passive"))
      (node (ref "D2") (pin "2") (pinfunction "A_2") (pintype "passive"))
      (node (ref "L1") (pin "2") (pinfunction "2_2") (pintype "passive"))
      (node (ref "R1") (pin "2") (pinfunction "2_2") (pintype "passive"))
    )
    (net (code "13") (name "Net-(LED1-DOUT)") (class "Default")
      (node (ref "LED1") (pin "3") (pinfunction "DOUT_3") (pintype "passive"))
      (node (ref "LED2") (pin "1") (pinfunction "DIN_1") (pintype "passive"))
    )
    (net (code "14") (name "Net-(LED2-DOUT)") (class "Default")
      (node (ref "LED2") (pin "3") (pinfunction "DOUT_3") (pintype "passive"))
      (node (ref "LED3") (pin "1") (pinfunction "DIN_1") (pintype "passive"))
    )
    (net (code "15") (name "Net-(LED3-DOUT)") (class "Default")
      (node (ref "LED3") (pin "3") (pinfunction "DOUT_3") (pintype "passive"))
      (node (ref "LED4") (pin "1") (pinfunction "DIN_1") (pintype "passive"))
    )
    (net (code "16") (name "Net-(LED4-DOUT)") (class "Default")
      (node (ref "LED4") (pin "3") (pinfunction "DOUT_3") (pintype "passive"))
      (node (ref "LED5") (pin "1") (pinfunction "DIN_1") (pintype "passive"))
    )
    (net (code "17") (name "Net-(LED5-DOUT)") (class "Default")
      (node (ref "LED5") (pin "3") (pinfunction "DOUT_3") (pintype "passive"))
      (node (ref "LED6") (pin "1") (pinfunction "DIN_1") (pintype "passive"))
    )
    (net (code "18") (name "Net-(LED6-DOUT)") (class "Default")
      (node (ref "LED6") (pin "3") (pinfunction "DOUT_3") (pintype "passive"))
      (node (ref "LED7") (pin "1") (pinfunction "DIN_1") (pintype "passive"))
    )
    (net (code "19") (name "Net-(LED7-DOUT)") (class "Default")
      (node (ref "LED7") (pin "3") (pinfunction "DOUT_3") (pintype "passive"))
      (node (ref "LED8") (pin "1") (pinfunction "DIN_1") (pintype "passive"))
    )
    (net (code "20") (name "Net-(LED8-DOUT)") (class "Default")
      (node (ref "LED8") (pin "3") (pinfunction "DOUT_3") (pintype "passive"))
      (node (ref "LED9") (pin "1") (pinfunction "DIN_1") (pintype "passive"))
    )
    (net (code "21") (name "Net-(LED10-DIN)") (class "Default")
      (node (ref "LED10") (pin "1") (pinfunction "DIN_1") (pintype "passive"))
      (node (ref "LED9") (pin "3") (pinfunction "DOUT_3") (pintype "passive"))
    )
    (net (code "22") (name "Net-(LED10-DOUT)") (class "Default")
      (node (ref "LED10") (pin "3") (pinfunction "DOUT_3") (pintype "passive"))
      (node (ref "LED11") (pin "1") (pinfunction "DIN_1") (pintype "passive"))
    )
    (net (code "23") (name "Net-(LED11-DOUT)") (class "Default")
      (node (ref "LED11") (pin "3") (pinfunction "DOUT_3") (pintype "passive"))
      (node (ref "LED12") (pin "1") (pinfunction "DIN_1") (pintype "passive"))
    )
    (net (code "24") (name "Net-(LED12-DOUT)") (class "Default")
      (node (ref "LED12") (pin "3") (pinfunction "DOUT_3") (pintype "passive"))
      (node (ref "LED13") (pin "1") (pinfunction "DIN_1") (pintype "passive"))
    )
    (net (code "25") (name "Net-(LED13-DOUT)") (class "Default")
      (node (ref "LED13") (pin "3") (pinfunction "DOUT_3") (pintype "passive"))
      (node (ref "LED14") (pin "1") (pinfunction "DIN_1") (pintype "passive"))
    )
    (net (code "26") (name "Net-(LED14-DOUT)") (class "Default")
      (node (ref "LED14") (pin "3") (pinfunction "DOUT_3") (pintype "passive"))
      (node (ref "LED15") (pin "1") (pinfunction "DIN_1") (pintype "passive"))
    )
    (net (code "27") (name "Net-(LED15-DOUT)") (class "Default")
      (node (ref "LED15") (pin "3") (pinfunction "DOUT_3") (pintype "passive"))
      (node (ref "LED16") (pin "1") (pinfunction "DIN_1") (pintype "passive"))
    )
    (net (code "28") (name "Net-(LED16-DOUT)") (class "Default")
      (node (ref "LED16") (pin "3") (pinfunction "DOUT_3") (pintype "passive"))
      (node (ref "LED17") (pin "1") (pinfunction "DIN_1") (pintype "passive"))
    )
    (net (code "29") (name "Net-(LED17-DOUT)") (class "Default")
      (node (ref "LED17") (pin "3") (pinfunction "DOUT_3") (pintype "passive"))
      (node (ref "LED18") (pin "1") (pinfunction "DIN_1") (pintype "passive"))
    )
    (net (code "30") (name "Net-(LED18-DOUT)") (class "Default")
      (node (ref "LED18") (pin "3") (pinfunction "DOUT_3") (pintype "passive"))
      (node (ref "LED19") (pin "1") (pinfunction "DIN_1") (pintype "passive"))
    )
    (net (code "31") (name "Net-(LED19-DOUT)") (class "Default")
      (node (ref "LED19") (pin "3") (pinfunction "DOUT_3") (pintype "passive"))
      (node (ref "LED20") (pin "1") (pinfunction "DIN_1") (pintype "passive"))
    )
    (net (code "32") (name "Net-(LED20-DOUT)") (class "Default")
      (node (ref "LED20") (pin "3") (pinfunction "DOUT_3") (pintype "passive"))
      (node (ref "LED21") (pin "1") (pinfunction "DIN_1") (pintype "passive"))
    )
    (net (code "33") (name "Net-(LED21-DOUT)") (class "Default")
      (node (ref "LED21") (pin "3") (pinfunction "DOUT_3") (pintype "passive"))
      (node (ref "LED22") (pin "1") (pinfunction "DIN_1") (pintype "passive"))
    )
    (net (code "34") (name "Net-(LED22-DOUT)") (class "Default")
      (node (ref "LED22") (pin "3") (pinfunction "DOUT_3") (pintype "passive"))
      (node (ref "LED23") (pin "1") (pinfunction "DIN_1") (pintype "passive"))
    )
    (net (code "35") (name "Net-(LED23-DOUT)") (class "Default")
      (node (ref "LED23") (pin "3") (pinfunction "DOUT_3") (pintype "passive"))
      (node (ref "LED24") (pin "1") (pinfunction "DIN_1") (pintype "passive"))
    )
    (net (code "36") (name "Net-(LED24-DOUT)") (class "Default")
      (node (ref "LED24") (pin "3") (pinfunction "DOUT_3") (pintype "passive"))
      (node (ref "LED25") (pin "1") (pinfunction "DIN_1") (pintype "passive"))
    )
    (net (code "37") (name "Net-(LED25-DOUT)") (class "Default")
      (node (ref "LED25") (pin "3") (pinfunction "DOUT_3") (pintype "passive"))
      (node (ref "LED26") (pin "1") (pinfunction "DIN_1") (pintype "passive"))
    )
    (net (code "38") (name "Net-(LED26-DOUT)") (class "Default")
      (node (ref "LED26") (pin "3") (pinfunction "DOUT_3") (pintype "passive"))
      (node (ref "LED27") (pin "1") (pinfunction "DIN_1") (pintype "passive"))
    )
    (net (code "39") (name "Net-(LED27-DOUT)") (class "Default")
      (node (ref "LED27") (pin "3") (pinfunction "DOUT_3") (pintype "passive"))
      (node (ref "LED28") (pin "1") (pinfunction "DIN_1") (pintype "passive"))
    )
    (net (code "40") (name "Net-(LED28-DOUT)") (class "Default")
      (node (ref "LED28") (pin "3") (pinfunction "DOUT_3") (pintype "passive"))
      (node (ref "LED29") (pin "1") (pinfunction "DIN_1") (pintype "passive"))
    )
    (net (code "41") (name "Net-(LED29-DOUT)") (class "Default")
      (node (ref "LED29") (pin "3") (pinfunction "DOUT_3") (pintype "passive"))
      (node (ref "LED30") (pin "1") (pinfunction "DIN_1") (pintype "passive"))
    )
    (net (code "42") (name "Net-(LED30-DOUT)") (class "Default")
      (node (ref "LED30") (pin "3") (pinfunction "DOUT_3") (pintype "passive"))
      (node (ref "LED31") (pin "1") (pinfunction "DIN_1") (pintype "passive"))
    )
    (net (code "43") (name "Net-(LED31-DOUT)") (class "Default")
      (node (ref "LED31") (pin "3") (pinfunction "DOUT_3") (pintype "passive"))
      (node (ref "LED32") (pin "1") (pinfunction "DIN_1") (pintype "passive"))
    )
    (net (code "44") (name "Net-(LED32-DOUT)") (class "Default")
      (node (ref "LED32") (pin "3") (pinfunction "DOUT_3") (pintype "passive"))
      (node (ref "LED33") (pin "1") (pinfunction "DIN_1") (pintype "passive"))
    )
    (net (code "45") (name "Net-(LED33-DOUT)") (class "Default")
      (node (ref "LED33") (pin "3") (pinfunction "DOUT_3") (pintype "passive"))
      (node (ref "LED34") (pin "1") (pinfunction "DIN_1") (pintype "passive"))
    )
    (net (code "46") (name "Net-(LED34-DOUT)") (class "Default")
      (node (ref "LED34") (pin "3") (pinfunction "DOUT_3") (pintype "passive"))
      (node (ref "LED35") (pin "1") (pinfunction "DIN_1") (pintype "passive"))
    )
    (net (code "47") (name "Net-(LED35-DOUT)") (class "Default")
      (node (ref "LED35") (pin "3") (pinfunction "DOUT_3") (pintype "passive"))
      (node (ref "LED36") (pin "1") (pinfunction "DIN_1") (pintype "passive"))
    )
    (net (code "48") (name "Net-(LED43-DOUT)") (class "Default")
      (node (ref "LED43") (pin "3") (pinfunction "DOUT_3") (pintype "passive"))
      (node (ref "LED44") (pin "1") (pinfunction "DIN_1") (pintype "passive"))
    )
    (net (code "49") (name "Net-(LED44-DOUT)") (class "Default")
      (node (ref "LED44") (pin "3") (pinfunction "DOUT_3") (pintype "passive"))
      (node (ref "LED45") (pin "1") (pinfunction "DIN_1") (pintype "passive"))
    )
    (net (code "50") (name "Net-(LED45-DOUT)") (class "Default")
      (node (ref "LED45") (pin "3") (pinfunction "DOUT_3") (pintype "passive"))
      (node (ref "LED46") (pin "1") (pinfunction "DIN_1") (pintype "passive"))
    )
    (net (code "51") (name "Net-(LED46-DOUT)") (class "Default")
      (node (ref "LED46") (pin "3") (pinfunction "DOUT_3") (pintype "passive"))
      (node (ref "LED47") (pin "1") (pinfunction "DIN_1") (pintype "passive"))
    )
    (net (code "52") (name "Net-(LED47-DOUT)") (class "Default")
      (node (ref "LED47") (pin "3") (pinfunction "DOUT_3") (pintype "passive"))
      (node (ref "LED48") (pin "1") (pinfunction "DIN_1") (pintype "passive"))
    )
    (net (code "53") (name "Net-(LED48-DOUT)") (class "Default")
      (node (ref "LED48") (pin "3") (pinfunction "DOUT_3") (pintype "passive"))
      (node (ref "LED49") (pin "1") (pinfunction "DIN_1") (pintype "passive"))
    )
    (net (code "54") (name "Net-(LED49-DOUT)") (class "Default")
      (node (ref "LED49") (pin "3") (pinfunction "DOUT_3") (pintype "passive"))
      (node (ref "LED50") (pin "1") (pinfunction "DIN_1") (pintype "passive"))
    )
    (net (code "55") (name "Net-(LED50-DOUT)") (class "Default")
      (node (ref "LED50") (pin "3") (pinfunction "DOUT_3") (pintype "passive"))
      (node (ref "LED51") (pin "1") (pinfunction "DIN_1") (pintype "passive"))
    )
    (net (code "56") (name "Net-(LED51-DOUT)") (class "Default")
      (node (ref "LED51") (pin "3") (pinfunction "DOUT_3") (pintype "passive"))
      (node (ref "LED52") (pin "1") (pinfunction "DIN_1") (pintype "passive"))
    )
    (net (code "57") (name "Net-(LED52-DOUT)") (class "Default")
      (node (ref "LED52") (pin "3") (pinfunction "DOUT_3") (pintype "passive"))
      (node (ref "LED53") (pin "1") (pinfunction "DIN_1") (pintype "passive"))
    )
    (net (code "58") (name "Net-(LED53-DOUT)") (class "Default")
      (node (ref "LED53") (pin "3") (pinfunction "DOUT_3") (pintype "passive"))
      (node (ref "LED54") (pin "1") (pinfunction "DIN_1") (pintype "passive"))
    )
    (net (code "59") (name "Net-(LED54-DOUT)") (class "Default")
      (node (ref "LED54") (pin "3") (pinfunction "DOUT_3") (pintype "passive"))
      (node (ref "LED55") (pin "1") (pinfunction "DIN_1") (pintype "passive"))
    )
    (net (code "60") (name "Net-(LED55-DOUT)") (class "Default")
      (node (ref "LED55") (pin "3") (pinfunction "DOUT_3") (pintype "passive"))
      (node (ref "LED56") (pin "1") (pinfunction "DIN_1") (pintype "passive"))
    )
    (net (code "61") (name "Net-(LED56-DOUT)") (class "Default")
      (node (ref "LED56") (pin "3") (pinfunction "DOUT_3") (pintype "passive"))
      (node (ref "LED57") (pin "1") (pinfunction "DIN_1") (pintype "passive"))
    )
    (net (code "62") (name "Net-(LED57-DOUT)") (class "Default")
      (node (ref "LED57") (pin "3") (pinfunction "DOUT_3") (pintype "passive"))
      (node (ref "LED58") (pin "1") (pinfunction "DIN_1") (pintype "passive"))
    )
    (net (code "63") (name "Net-(LED58-DOUT)") (class "Default")
      (node (ref "LED58") (pin "3") (pinfunction "DOUT_3") (pintype "passive"))
      (node (ref "LED59") (pin "1") (pinfunction "DIN_1") (pintype "passive"))
    )
    (net (code "64") (name "Net-(LED59-DOUT)") (class "Default")
      (node (ref "LED59") (pin "3") (pinfunction "DOUT_3") (pintype "passive"))
      (node (ref "LED60") (pin "1") (pinfunction "DIN_1") (pintype "passive"))
    )
    (net (code "65") (name "Net-(LED60-DOUT)") (class "Default")
      (node (ref "LED60") (pin "3") (pinfunction "DOUT_3") (pintype "passive"))
      (node (ref "LED61") (pin "1") (pinfunction "DIN_1") (pintype "passive"))
    )
    (net (code "66") (name "Net-(LED61-DOUT)") (class "Default")
      (node (ref "LED61") (pin "3") (pinfunction "DOUT_3") (pintype "passive"))
      (node (ref "LED62") (pin "1") (pinfunction "DIN_1") (pintype "passive"))
    )
    (net (code "67") (name "Net-(LED62-DOUT)") (class "Default")
      (node (ref "LED62") (pin "3") (pinfunction "DOUT_3") (pintype "passive"))
      (node (ref "LED63") (pin "1") (pinfunction "DIN_1") (pintype "passive"))
    )
    (net (code "68") (name "Net-(LED63-DOUT)") (class "Default")
      (node (ref "LED63") (pin "3") (pinfunction "DOUT_3") (pintype "passive"))
      (node (ref "LED64") (pin "1") (pinfunction "DIN_1") (pintype "passive"))
    )
    (net (code "69") (name "Net-(LED64-DOUT)") (class "Default")
      (node (ref "LED64") (pin "3") (pinfunction "DOUT_3") (pintype "passive"))
      (node (ref "LED65") (pin "1") (pinfunction "DIN_1") (pintype "passive"))
    )
    (net (code "70") (name "Net-(LED65-DOUT)") (class "Default")
      (node (ref "LED65") (pin "3") (pinfunction "DOUT_3") (pintype "passive"))
      (node (ref "LED66") (pin "1") (pinfunction "DIN_1") (pintype "passive"))
    )
    (net (code "71") (name "Net-(LED66-DOUT)") (class "Default")
      (node (ref "LED66") (pin "3") (pinfunction "DOUT_3") (pintype "passive"))
      (node (ref "LED67") (pin "1") (pinfunction "DIN_1") (pintype "passive"))
    )
    (net (code "72") (name "Net-(LED67-DOUT)") (class "Default")
      (node (ref "LED67") (pin "3") (pinfunction "DOUT_3") (pintype "passive"))
      (node (ref "LED68") (pin "1") (pinfunction "DIN_1") (pintype "passive"))
    )
    (net (code "73") (name "Net-(LED68-DOUT)") (class "Default")
      (node (ref "LED68") (pin "3") (pinfunction "DOUT_3") (pintype "passive"))
      (node (ref "LED69") (pin "1") (pinfunction "DIN_1") (pintype "passive"))
    )
    (net (code "74") (name "Net-(LED69-DOUT)") (class "Default")
      (node (ref "LED69") (pin "3") (pinfunction "DOUT_3") (pintype "passive"))
      (node (ref "LED70") (pin "1") (pinfunction "DIN_1") (pintype "passive"))
    )
    (net (code "75") (name "Net-(LED70-DOUT)") (class "Default")
      (node (ref "LED70") (pin "3") (pinfunction "DOUT_3") (pintype "passive"))
      (node (ref "LED71") (pin "1") (pinfunction "DIN_1") (pintype "passive"))
    )
    (net (code "76") (name "Net-(LED71-DOUT)") (class "Default")
      (node (ref "LED71") (pin "3") (pinfunction "DOUT_3") (pintype "passive"))
      (node (ref "LED72") (pin "1") (pinfunction "DIN_1") (pintype "passive"))
    )
    (net (code "77") (name "Net-(LED72-DOUT)") (class "Default")
      (node (ref "LED72") (pin "3") (pinfunction "DOUT_3") (pintype "passive"))
      (node (ref "LED73") (pin "1") (pinfunction "DIN_1") (pintype "passive"))
    )
    (net (code "78") (name "Net-(LED73-DOUT)") (class "Default")
      (node (ref "LED73") (pin "3") (pinfunction "DOUT_3") (pintype "passive"))
      (node (ref "LED74") (pin "1") (pinfunction "DIN_1") (pintype "passive"))
    )
    (net (code "79") (name "Net-(LED74-DOUT)") (class "Default")
      (node (ref "LED74") (pin "3") (pinfunction "DOUT_3") (pintype "passive"))
      (node (ref "LED75") (pin "1") (pinfunction "DIN_1") (pintype "passive"))
    )
    (net (code "80") (name "Net-(LED75-DOUT)") (class "Default")
      (node (ref "LED75") (pin "3") (pinfunction "DOUT_3") (pintype "passive"))
      (node (ref "LED76") (pin "1") (pinfunction "DIN_1") (pintype "passive"))
    )
    (net (code "81") (name "Net-(LED76-DOUT)") (class "Default")
      (node (ref "LED76") (pin "3") (pinfunction "DOUT_3") (pintype "passive"))
      (node (ref "LED77") (pin "1") (pinfunction "DIN_1") (pintype "passive"))
    )
    (net (code "82") (name "Net-(LED77-DOUT)") (class "Default")
      (node (ref "LED77") (pin "3") (pinfunction "DOUT_3") (pintype "passive"))
      (node (ref "LED78") (pin "1") (pinfunction "DIN_1") (pintype "passive"))
    )
    (net (code "83") (name "Net-(P2-Pad1)") (class "Default")
      (node (ref "P2") (pin "1") (pinfunction "1_1") (pintype "passive"))
      (node (ref "R3") (pin "1") (pinfunction "1_1") (pintype "passive"))
    )
    (net (code "84") (name "Net-(P3-Pad2)") (class "Default")
      (node (ref "P3") (pin "2") (pinfunction "2_2") (pintype "passive"))
      (node (ref "R4") (pin "1") (pinfunction "1_1") (pintype "passive"))
    )
    (net (code "85") (name "Net-(P4-Pad2)") (class "Default")
      (node (ref "P4") (pin "2") (pinfunction "2_2") (pintype "passive"))
      (node (ref "R7") (pin "2") (pinfunction "2_2") (pintype "passive"))
    )
    (net (code "86") (name "Net-(P5-Pad2)") (class "Default")
      (node (ref "P5") (pin "2") (pinfunction "2_2") (pintype "passive"))
      (node (ref "R8") (pin "2") (pinfunction "2_2") (pintype "passive"))
    )
    (net (code "87") (name "Net-(U1-BOOT)") (class "Default")
      (node (ref "C2") (pin "1") (pinfunction "1_1") (pintype "passive"))
      (node (ref "U1") (pin "6") (pinfunction "BOOT_6") (pintype "passive"))
    )
    (net (code "88") (name "Net-(U1-FB)") (class "Default")
      (node (ref "C3") (pin "1") (pinfunction "1_1") (pintype "passive"))
      (node (ref "R1") (pin "1") (pinfunction "1_1") (pintype "passive"))
      (node (ref "R2") (pin "2") (pinfunction "2_2") (pintype "passive"))
      (node (ref "U1") (pin "4") (pinfunction "FB_4") (pintype "passive"))
    )
    (net (code "89") (name "Net-(U1-SW)") (class "Default")
      (node (ref "C2") (pin "2") (pinfunction "2_2") (pintype "passive"))
      (node (ref "L1") (pin "1") (pinfunction "1_1") (pintype "passive"))
      (node (ref "U1") (pin "2") (pinfunction "SW_2") (pintype "passive"))
    )
    (net (code "90") (name "Net-(U2-GP2)") (class "Default")
      (node (ref "C47") (pin "2") (pinfunction "2_2") (pintype "passive"))
      (node (ref "R7") (pin "1") (pinfunction "1_1") (pintype "passive"))
      (node (ref "R9") (pin "2") (pinfunction "2_2") (pintype "passive"))
      (node (ref "U2") (pin "3") (pinfunction "GP2_3") (pintype "passive"))
    )
    (net (code "91") (name "Net-(U2-GP3)") (class "Default")
      (node (ref "C48") (pin "2") (pinfunction "2_2") (pintype "passive"))
      (node (ref "R10") (pin "2") (pinfunction "2_2") (pintype "passive"))
      (node (ref "R8") (pin "1") (pinfunction "1_1") (pintype "passive"))
      (node (ref "U2") (pin "4") (pinfunction "GP3_4") (pintype "passive"))
    )
    (net (code "92") (name "Net-(U2-GP8)") (class "Default")
      (node (ref "SW1") (pin "1") (pinfunction "1_1") (pintype "passive"))
      (node (ref "SW1") (pin "2") (pinfunction "2_2") (pintype "passive"))
      (node (ref "U2") (pin "9") (pinfunction "GP8_9") (pintype "passive"))
    )
    (net (code "93") (name "Net-(U2-GP27)") (class "Default")
      (node (ref "C7") (pin "2") (pinfunction "2_2") (pintype "passive"))
      (node (ref "R13") (pin "1") (pinfunction "1_1") (pintype "passive"))
      (node (ref "R14") (pin "2") (pinfunction "2_2") (pintype "passive"))
      (node (ref "R6") (pin "2") (pinfunction "2_2") (pintype "passive"))
      (node (ref "U2") (pin "18") (pinfunction "GP27_18") (pintype "passive"))
    )
    (net (code "94") (name "Net-(U2-GP28)") (class "Default")
      (node (ref "C8") (pin "2") (pinfunction "2_2") (pintype "passive"))
      (node (ref "R11") (pin "1") (pinfunction "1_1") (pintype "passive"))
      (node (ref "R12") (pin "2") (pinfunction "2_2") (pintype "passive"))
      (node (ref "R5") (pin "2") (pinfunction "2_2") (pintype "passive"))
      (node (ref "U2") (pin "19") (pinfunction "GP28_19") (pintype "passive"))
    )
    (net (code "95") (name "unconnected-(LED36-DOUT-Pad3)") (class "Default")
      (node (ref "LED36") (pin "3") (pinfunction "DOUT_3") (pintype "passive+no_connect"))
    )
    (net (code "96") (name "unconnected-(LED78-DOUT-Pad3)") (class "Default")
      (node (ref "LED78") (pin "3") (pinfunction "DOUT_3") (pintype "passive+no_connect"))
    )
    (net (code "97") (name "unconnected-(U1-EN-Pad5)") (class "Default")
      (node (ref "U1") (pin "5") (pinfunction "EN_5") (pintype "passive+no_connect"))
    )
    (net (code "98") (name "unconnected-(U2-GP0-Pad1)") (class "Default")
      (node (ref "U2") (pin "1") (pinfunction "GP0_1") (pintype "passive+no_connect"))
    )
    (net (code "99") (name "unconnected-(U2-GP1-Pad2)") (class "Default")
      (node (ref "U2") (pin "2") (pinfunction "GP1_2") (pintype "passive+no_connect"))
    )
    (net (code "100") (name "unconnected-(U2-GP4-Pad5)") (class "Default")
      (node (ref "U2") (pin "5") (pinfunction "GP4_5") (pintype "passive+no_connect"))
    )
    (net (code "101") (name "unconnected-(U2-GP5-Pad6)") (class "Default")
      (node (ref "U2") (pin "6") (pinfunction "GP5_6") (pintype "passive+no_connect"))
    )
    (net (code "102") (name "unconnected-(U2-GP6-Pad7)") (class "Default")
      (node (ref "U2") (pin "7") (pinfunction "GP6_7") (pintype "passive+no_connect"))
    )
    (net (code "103") (name "unconnected-(U2-GP7-Pad8)") (class "Default")
      (node (ref "U2") (pin "8") (pinfunction "GP7_8") (pintype "passive+no_connect"))
    )
    (net (code "104") (name "unconnected-(U2-GP9-Pad10)") (class "Default")
      (node (ref "U2") (pin "10") (pinfunction "GP9_10") (pintype "passive+no_connect"))
    )
    (net (code "105") (name "unconnected-(U2-GP10-Pad11)") (class "Default")
      (node (ref "U2") (pin "11") (pinfunction "GP10_11") (pintype "passive+no_connect"))
    )
    (net (code "106") (name "unconnected-(U2-GP11-Pad12)") (class "Default")
      (node (ref "U2") (pin "12") (pinfunction "GP11_12") (pintype "passive+no_connect"))
    )
    (net (code "107") (name "unconnected-(U2-GP12-Pad13)") (class "Default")
      (node (ref "U2") (pin "13") (pinfunction "GP12_13") (pintype "passive+no_connect"))
    )
    (net (code "108") (name "unconnected-(U2-GP13-Pad14)") (class "Default")
      (node (ref "U2") (pin "14") (pinfunction "GP13_14") (pintype "passive+no_connect"))
    )
    (net (code "109") (name "unconnected-(U2-GP26-Pad17)") (class "Default")
      (node (ref "U2") (pin "17") (pinfunction "GP26_17") (pintype "passive+no_connect"))
    )
    (net (code "110") (name "unconnected-(U2-GP29-Pad20)") (class "Default")
      (node (ref "U2") (pin "20") (pinfunction "GP29_20") (pintype "passive+no_connect"))
    )
  )
)
